# SCH_61.net
KiCad netlist of a schematic drawn in EasyEDA
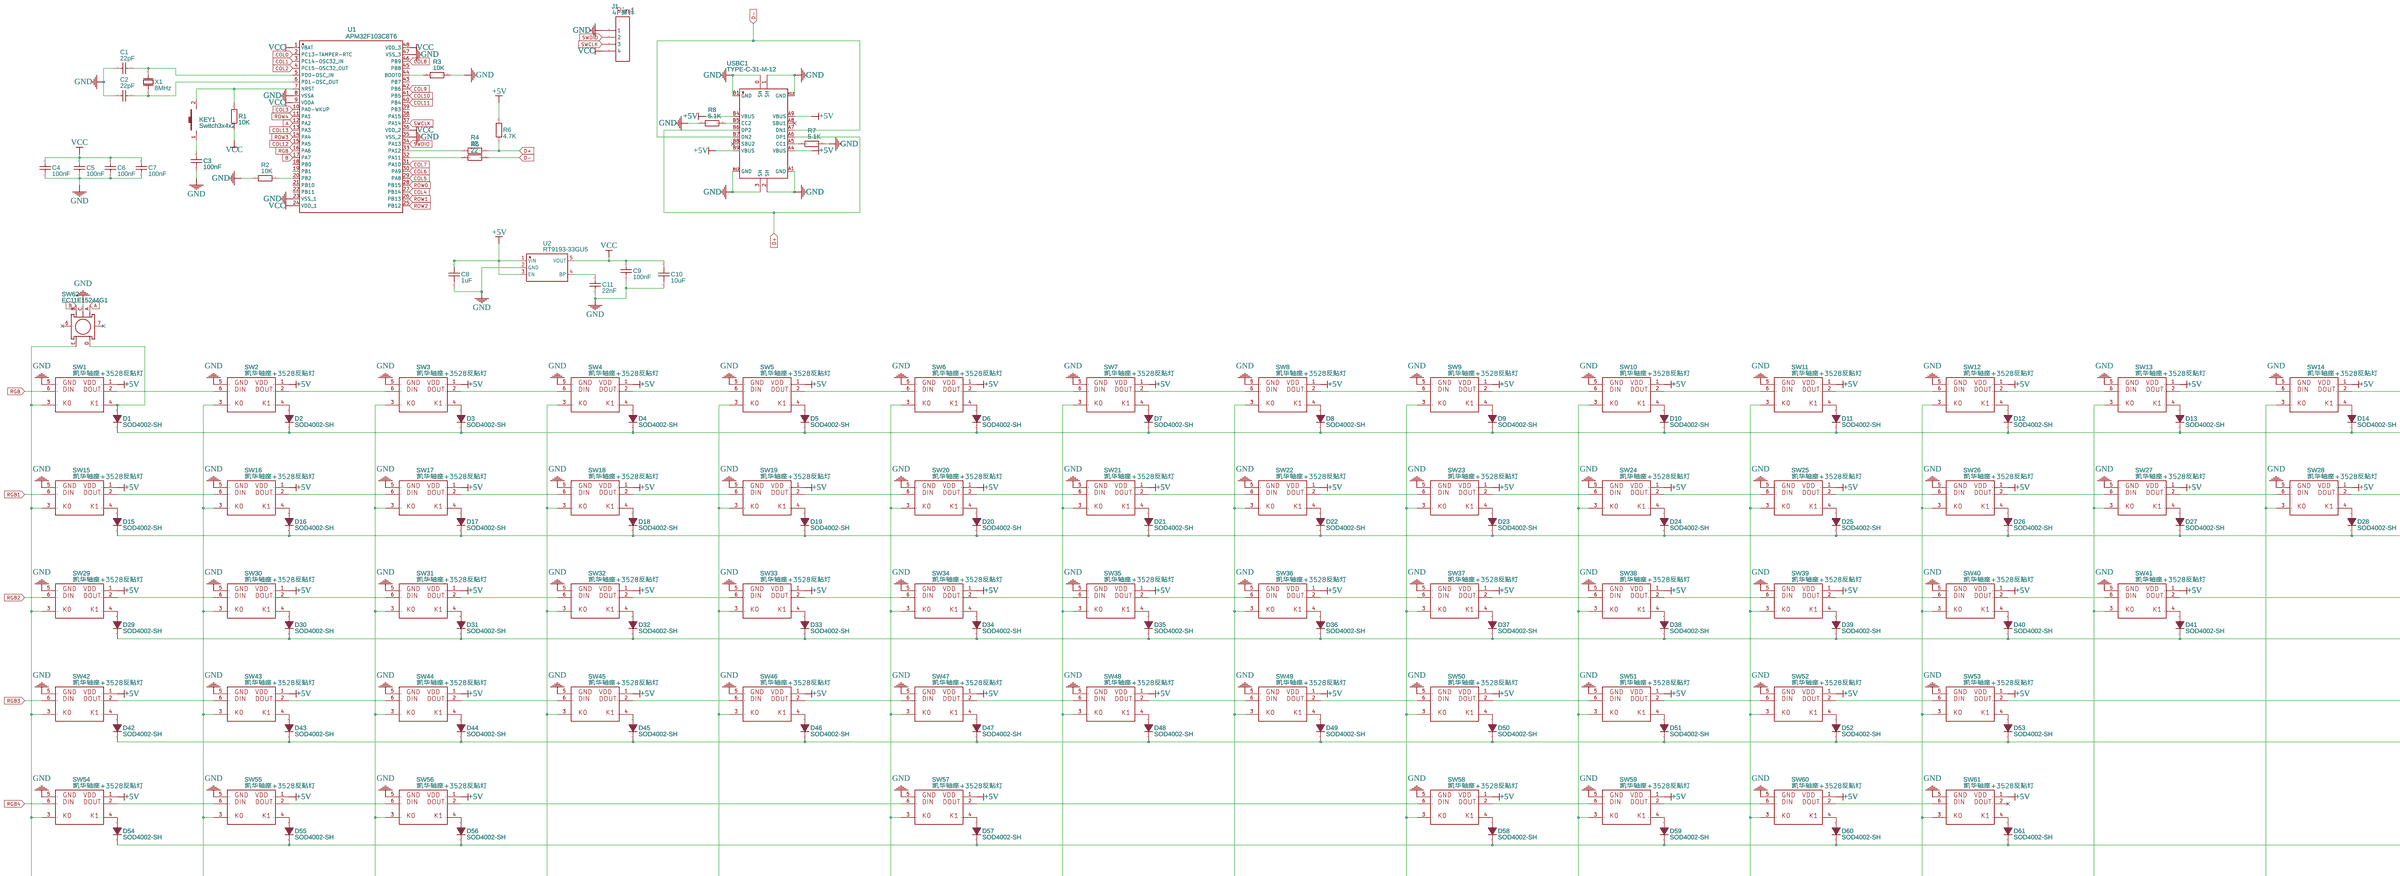
[diagram p0: schematic sheet]

(export (version "E")
  (design (tool "Eeschema 10.0.6"))
  (components
    (comp (ref "C1")
      (value "22pF")
      (fields
        (field (name "BOM_Manufacturer Part") "0805CG220J500NT")
        (field (name "BOM_Supplier Part") "C38143")
      )
      (libsource (lib "") (part "0805CG220J500NT"))
    )
    (comp (ref "C2")
      (value "22pF")
      (fields
        (field (name "BOM_Manufacturer Part") "0805CG220J500NT")
        (field (name "BOM_Supplier Part") "C38143")
      )
      (libsource (lib "") (part "0805CG220J500NT"))
    )
    (comp (ref "C3")
      (value "100nF")
      (fields
        (field (name "BOM_Manufacturer Part") "CL21B104KBCNNNC")
        (field (name "BOM_Supplier Part") "C1711")
      )
      (libsource (lib "") (part "CL21B104KBCNNNC"))
    )
    (comp (ref "C4")
      (value "100nF")
      (fields
        (field (name "BOM_Manufacturer Part") "CL21B104KBCNNNC")
        (field (name "BOM_Supplier Part") "C1711")
      )
      (libsource (lib "") (part "CL21B104KBCNNNC"))
    )
    (comp (ref "C5")
      (value "100nF")
      (fields
        (field (name "BOM_Manufacturer Part") "CL21B104KBCNNNC")
        (field (name "BOM_Supplier Part") "C1711")
      )
      (libsource (lib "") (part "CL21B104KBCNNNC"))
    )
    (comp (ref "C6")
      (value "100nF")
      (fields
        (field (name "BOM_Manufacturer Part") "CL21B104KBCNNNC")
        (field (name "BOM_Supplier Part") "C1711")
      )
      (libsource (lib "") (part "CL21B104KBCNNNC"))
    )
    (comp (ref "C7")
      (value "100nF")
      (fields
        (field (name "BOM_Manufacturer Part") "CL21B104KBCNNNC")
        (field (name "BOM_Supplier Part") "C1711")
      )
      (libsource (lib "") (part "CL21B104KBCNNNC"))
    )
    (comp (ref "C8")
      (value "1uF")
      (fields
        (field (name "BOM_Manufacturer Part") "CL21B105KBFVPNE")
        (field (name "BOM_Supplier Part") "C307362")
      )
      (libsource (lib "") (part "CL21B105KBFVPNE"))
    )
    (comp (ref "C9")
      (value "100nF")
      (fields
        (field (name "BOM_Manufacturer Part") "CL21B104KBCNNNC")
        (field (name "BOM_Supplier Part") "C1711")
      )
      (libsource (lib "") (part "CL21B104KBCNNNC"))
    )
    (comp (ref "C10")
      (value "10uF")
      (fields
        (field (name "BOM_Manufacturer Part") "CL21B106KPQNFNE")
        (field (name "BOM_Supplier Part") "C307538")
      )
      (libsource (lib "") (part "CL21B106KPQNFNE"))
    )
    (comp (ref "C11")
      (value "22nF")
      (fields
        (field (name "BOM_Manufacturer Part") "CL21B223KBANNNC")
        (field (name "BOM_Supplier Part") "C1729")
      )
      (libsource (lib "") (part "CL21B223KBANNNC"))
    )
    (comp (ref "D1")
      (value "SOD4002-SH")
      (fields (field (name "BOM_Supplier Part") "C154996"))
      (libsource (lib "") (part "SOD4002-SH"))
    )
    (comp (ref "D2")
      (value "SOD4002-SH")
      (fields (field (name "BOM_Supplier Part") "C154996"))
      (libsource (lib "") (part "SOD4002-SH"))
    )
    (comp (ref "D3")
      (value "SOD4002-SH")
      (fields (field (name "BOM_Supplier Part") "C154996"))
      (libsource (lib "") (part "SOD4002-SH"))
    )
    (comp (ref "D4")
      (value "SOD4002-SH")
      (fields (field (name "BOM_Supplier Part") "C154996"))
      (libsource (lib "") (part "SOD4002-SH"))
    )
    (comp (ref "D5")
      (value "SOD4002-SH")
      (fields (field (name "BOM_Supplier Part") "C154996"))
      (libsource (lib "") (part "SOD4002-SH"))
    )
    (comp (ref "D6")
      (value "SOD4002-SH")
      (fields (field (name "BOM_Supplier Part") "C154996"))
      (libsource (lib "") (part "SOD4002-SH"))
    )
    (comp (ref "D7")
      (value "SOD4002-SH")
      (fields (field (name "BOM_Supplier Part") "C154996"))
      (libsource (lib "") (part "SOD4002-SH"))
    )
    (comp (ref "D8")
      (value "SOD4002-SH")
      (fields (field (name "BOM_Supplier Part") "C154996"))
      (libsource (lib "") (part "SOD4002-SH"))
    )
    (comp (ref "D9")
      (value "SOD4002-SH")
      (fields (field (name "BOM_Supplier Part") "C154996"))
      (libsource (lib "") (part "SOD4002-SH"))
    )
    (comp (ref "D10")
      (value "SOD4002-SH")
      (fields (field (name "BOM_Supplier Part") "C154996"))
      (libsource (lib "") (part "SOD4002-SH"))
    )
    (comp (ref "D11")
      (value "SOD4002-SH")
      (fields (field (name "BOM_Supplier Part") "C154996"))
      (libsource (lib "") (part "SOD4002-SH"))
    )
    (comp (ref "D12")
      (value "SOD4002-SH")
      (fields (field (name "BOM_Supplier Part") "C154996"))
      (libsource (lib "") (part "SOD4002-SH"))
    )
    (comp (ref "D13")
      (value "SOD4002-SH")
      (fields (field (name "BOM_Supplier Part") "C154996"))
      (libsource (lib "") (part "SOD4002-SH"))
    )
    (comp (ref "D14")
      (value "SOD4002-SH")
      (fields (field (name "BOM_Supplier Part") "C154996"))
      (libsource (lib "") (part "SOD4002-SH"))
    )
    (comp (ref "D15")
      (value "SOD4002-SH")
      (fields (field (name "BOM_Supplier Part") "C154996"))
      (libsource (lib "") (part "SOD4002-SH"))
    )
    (comp (ref "D16")
      (value "SOD4002-SH")
      (fields (field (name "BOM_Supplier Part") "C154996"))
      (libsource (lib "") (part "SOD4002-SH"))
    )
    (comp (ref "D17")
      (value "SOD4002-SH")
      (fields (field (name "BOM_Supplier Part") "C154996"))
      (libsource (lib "") (part "SOD4002-SH"))
    )
    (comp (ref "D18")
      (value "SOD4002-SH")
      (fields (field (name "BOM_Supplier Part") "C154996"))
      (libsource (lib "") (part "SOD4002-SH"))
    )
    (comp (ref "D19")
      (value "SOD4002-SH")
      (fields (field (name "BOM_Supplier Part") "C154996"))
      (libsource (lib "") (part "SOD4002-SH"))
    )
    (comp (ref "D20")
      (value "SOD4002-SH")
      (fields (field (name "BOM_Supplier Part") "C154996"))
      (libsource (lib "") (part "SOD4002-SH"))
    )
    (comp (ref "D21")
      (value "SOD4002-SH")
      (fields (field (name "BOM_Supplier Part") "C154996"))
      (libsource (lib "") (part "SOD4002-SH"))
    )
    (comp (ref "D22")
      (value "SOD4002-SH")
      (fields (field (name "BOM_Supplier Part") "C154996"))
      (libsource (lib "") (part "SOD4002-SH"))
    )
    (comp (ref "D23")
      (value "SOD4002-SH")
      (fields (field (name "BOM_Supplier Part") "C154996"))
      (libsource (lib "") (part "SOD4002-SH"))
    )
    (comp (ref "D24")
      (value "SOD4002-SH")
      (fields (field (name "BOM_Supplier Part") "C154996"))
      (libsource (lib "") (part "SOD4002-SH"))
    )
    (comp (ref "D25")
      (value "SOD4002-SH")
      (fields (field (name "BOM_Supplier Part") "C154996"))
      (libsource (lib "") (part "SOD4002-SH"))
    )
    (comp (ref "D26")
      (value "SOD4002-SH")
      (fields (field (name "BOM_Supplier Part") "C154996"))
      (libsource (lib "") (part "SOD4002-SH"))
    )
    (comp (ref "D27")
      (value "SOD4002-SH")
      (fields (field (name "BOM_Supplier Part") "C154996"))
      (libsource (lib "") (part "SOD4002-SH"))
    )
    (comp (ref "D28")
      (value "SOD4002-SH")
      (fields (field (name "BOM_Supplier Part") "C154996"))
      (libsource (lib "") (part "SOD4002-SH"))
    )
    (comp (ref "D29")
      (value "SOD4002-SH")
      (fields (field (name "BOM_Supplier Part") "C154996"))
      (libsource (lib "") (part "SOD4002-SH"))
    )
    (comp (ref "D30")
      (value "SOD4002-SH")
      (fields (field (name "BOM_Supplier Part") "C154996"))
      (libsource (lib "") (part "SOD4002-SH"))
    )
    (comp (ref "D31")
      (value "SOD4002-SH")
      (fields (field (name "BOM_Supplier Part") "C154996"))
      (libsource (lib "") (part "SOD4002-SH"))
    )
    (comp (ref "D32")
      (value "SOD4002-SH")
      (fields (field (name "BOM_Supplier Part") "C154996"))
      (libsource (lib "") (part "SOD4002-SH"))
    )
    (comp (ref "D33")
      (value "SOD4002-SH")
      (fields (field (name "BOM_Supplier Part") "C154996"))
      (libsource (lib "") (part "SOD4002-SH"))
    )
    (comp (ref "D34")
      (value "SOD4002-SH")
      (fields (field (name "BOM_Supplier Part") "C154996"))
      (libsource (lib "") (part "SOD4002-SH"))
    )
    (comp (ref "D35")
      (value "SOD4002-SH")
      (fields (field (name "BOM_Supplier Part") "C154996"))
      (libsource (lib "") (part "SOD4002-SH"))
    )
    (comp (ref "D36")
      (value "SOD4002-SH")
      (fields (field (name "BOM_Supplier Part") "C154996"))
      (libsource (lib "") (part "SOD4002-SH"))
    )
    (comp (ref "D37")
      (value "SOD4002-SH")
      (fields (field (name "BOM_Supplier Part") "C154996"))
      (libsource (lib "") (part "SOD4002-SH"))
    )
    (comp (ref "D38")
      (value "SOD4002-SH")
      (fields (field (name "BOM_Supplier Part") "C154996"))
      (libsource (lib "") (part "SOD4002-SH"))
    )
    (comp (ref "D39")
      (value "SOD4002-SH")
      (fields (field (name "BOM_Supplier Part") "C154996"))
      (libsource (lib "") (part "SOD4002-SH"))
    )
    (comp (ref "D40")
      (value "SOD4002-SH")
      (fields (field (name "BOM_Supplier Part") "C154996"))
      (libsource (lib "") (part "SOD4002-SH"))
    )
    (comp (ref "D41")
      (value "SOD4002-SH")
      (fields (field (name "BOM_Supplier Part") "C154996"))
      (libsource (lib "") (part "SOD4002-SH"))
    )
    (comp (ref "D42")
      (value "SOD4002-SH")
      (fields (field (name "BOM_Supplier Part") "C154996"))
      (libsource (lib "") (part "SOD4002-SH"))
    )
    (comp (ref "D43")
      (value "SOD4002-SH")
      (fields (field (name "BOM_Supplier Part") "C154996"))
      (libsource (lib "") (part "SOD4002-SH"))
    )
    (comp (ref "D44")
      (value "SOD4002-SH")
      (fields (field (name "BOM_Supplier Part") "C154996"))
      (libsource (lib "") (part "SOD4002-SH"))
    )
    (comp (ref "D45")
      (value "SOD4002-SH")
      (fields (field (name "BOM_Supplier Part") "C154996"))
      (libsource (lib "") (part "SOD4002-SH"))
    )
    (comp (ref "D46")
      (value "SOD4002-SH")
      (fields (field (name "BOM_Supplier Part") "C154996"))
      (libsource (lib "") (part "SOD4002-SH"))
    )
    (comp (ref "D47")
      (value "SOD4002-SH")
      (fields (field (name "BOM_Supplier Part") "C154996"))
      (libsource (lib "") (part "SOD4002-SH"))
    )
    (comp (ref "D48")
      (value "SOD4002-SH")
      (fields (field (name "BOM_Supplier Part") "C154996"))
      (libsource (lib "") (part "SOD4002-SH"))
    )
    (comp (ref "D49")
      (value "SOD4002-SH")
      (fields (field (name "BOM_Supplier Part") "C154996"))
      (libsource (lib "") (part "SOD4002-SH"))
    )
    (comp (ref "D50")
      (value "SOD4002-SH")
      (fields (field (name "BOM_Supplier Part") "C154996"))
      (libsource (lib "") (part "SOD4002-SH"))
    )
    (comp (ref "D51")
      (value "SOD4002-SH")
      (fields (field (name "BOM_Supplier Part") "C154996"))
      (libsource (lib "") (part "SOD4002-SH"))
    )
    (comp (ref "D52")
      (value "SOD4002-SH")
      (fields (field (name "BOM_Supplier Part") "C154996"))
      (libsource (lib "") (part "SOD4002-SH"))
    )
    (comp (ref "D53")
      (value "SOD4002-SH")
      (fields (field (name "BOM_Supplier Part") "C154996"))
      (libsource (lib "") (part "SOD4002-SH"))
    )
    (comp (ref "D54")
      (value "SOD4002-SH")
      (fields (field (name "BOM_Supplier Part") "C154996"))
      (libsource (lib "") (part "SOD4002-SH"))
    )
    (comp (ref "D55")
      (value "SOD4002-SH")
      (fields (field (name "BOM_Supplier Part") "C154996"))
      (libsource (lib "") (part "SOD4002-SH"))
    )
    (comp (ref "D56")
      (value "SOD4002-SH")
      (fields (field (name "BOM_Supplier Part") "C154996"))
      (libsource (lib "") (part "SOD4002-SH"))
    )
    (comp (ref "D57")
      (value "SOD4002-SH")
      (fields (field (name "BOM_Supplier Part") "C154996"))
      (libsource (lib "") (part "SOD4002-SH"))
    )
    (comp (ref "D58")
      (value "SOD4002-SH")
      (fields (field (name "BOM_Supplier Part") "C154996"))
      (libsource (lib "") (part "SOD4002-SH"))
    )
    (comp (ref "D59")
      (value "SOD4002-SH")
      (fields (field (name "BOM_Supplier Part") "C154996"))
      (libsource (lib "") (part "SOD4002-SH"))
    )
    (comp (ref "D60")
      (value "SOD4002-SH")
      (fields (field (name "BOM_Supplier Part") "C154996"))
      (libsource (lib "") (part "SOD4002-SH"))
    )
    (comp (ref "D61")
      (value "SOD4002-SH")
      (fields (field (name "BOM_Supplier Part") "C154996"))
      (libsource (lib "") (part "SOD4002-SH"))
    )
    (comp (ref "J1") (value "4P排针") (libsource (lib "") (part "4P排针")))
    (comp (ref "KEY1")
      (value "Switch3x4x2")
      (fields (field (name "BOM_Supplier Part") "C26638"))
      (libsource (lib "") (part "Switch3x4x2"))
    )
    (comp (ref "R1")
      (value "10K")
      (fields
        (field (name "BOM_Manufacturer Part") "RC0805FR-0710KL")
        (field (name "BOM_Supplier Part") "C84376")
      )
      (libsource (lib "") (part "RC0805FR-0710KL"))
    )
    (comp (ref "R2")
      (value "10K")
      (fields
        (field (name "BOM_Manufacturer Part") "RC0805FR-0710KL")
        (field (name "BOM_Supplier Part") "C84376")
      )
      (libsource (lib "") (part "RC0805FR-0710KL_1"))
    )
    (comp (ref "R3")
      (value "10K")
      (fields
        (field (name "BOM_Manufacturer Part") "RC0805FR-0710KL")
        (field (name "BOM_Supplier Part") "C84376")
      )
      (libsource (lib "") (part "RC0805FR-0710KL_1"))
    )
    (comp (ref "R4")
      (value "22")
      (fields
        (field (name "BOM_Manufacturer Part") "RC0805FR-0722RL")
        (field (name "BOM_Supplier Part") "C107702")
      )
      (libsource (lib "") (part "RC0805FR-0722RL"))
    )
    (comp (ref "R5")
      (value "22")
      (fields
        (field (name "BOM_Manufacturer Part") "RC0805FR-0722RL")
        (field (name "BOM_Supplier Part") "C107702")
      )
      (libsource (lib "") (part "RC0805FR-0722RL"))
    )
    (comp (ref "R6")
      (value "4.7K")
      (fields
        (field (name "BOM_Manufacturer Part") "RC0805JR-074K7L")
        (field (name "BOM_Supplier Part") "C105427")
      )
      (libsource (lib "") (part "RC0805JR-074K7L"))
    )
    (comp (ref "R7")
      (value "5.1K")
      (fields
        (field (name "BOM_Manufacturer Part") "RC0805FR-075K1L")
        (field (name "BOM_Supplier Part") "C84375")
      )
      (libsource (lib "") (part "RC0805FR-075K1L"))
    )
    (comp (ref "R8")
      (value "5.1K")
      (fields
        (field (name "BOM_Manufacturer Part") "RC0805FR-075K1L")
        (field (name "BOM_Supplier Part") "C84375")
      )
      (libsource (lib "") (part "RC0805FR-075K1L"))
    )
    (comp (ref "SW1") (value "凯华轴座+3528反贴灯") (libsource (lib "") (part "凯华轴座+3528反贴灯")))
    (comp (ref "SW2") (value "凯华轴座+3528反贴灯") (libsource (lib "") (part "凯华轴座+3528反贴灯")))
    (comp (ref "SW3") (value "凯华轴座+3528反贴灯") (libsource (lib "") (part "凯华轴座+3528反贴灯")))
    (comp (ref "SW4") (value "凯华轴座+3528反贴灯") (libsource (lib "") (part "凯华轴座+3528反贴灯")))
    (comp (ref "SW5") (value "凯华轴座+3528反贴灯") (libsource (lib "") (part "凯华轴座+3528反贴灯")))
    (comp (ref "SW6") (value "凯华轴座+3528反贴灯") (libsource (lib "") (part "凯华轴座+3528反贴灯")))
    (comp (ref "SW7") (value "凯华轴座+3528反贴灯") (libsource (lib "") (part "凯华轴座+3528反贴灯")))
    (comp (ref "SW8") (value "凯华轴座+3528反贴灯") (libsource (lib "") (part "凯华轴座+3528反贴灯")))
    (comp (ref "SW9") (value "凯华轴座+3528反贴灯") (libsource (lib "") (part "凯华轴座+3528反贴灯")))
    (comp (ref "SW10") (value "凯华轴座+3528反贴灯") (libsource (lib "") (part "凯华轴座+3528反贴灯")))
    (comp (ref "SW11") (value "凯华轴座+3528反贴灯") (libsource (lib "") (part "凯华轴座+3528反贴灯")))
    (comp (ref "SW12") (value "凯华轴座+3528反贴灯") (libsource (lib "") (part "凯华轴座+3528反贴灯")))
    (comp (ref "SW13") (value "凯华轴座+3528反贴灯") (libsource (lib "") (part "凯华轴座+3528反贴灯")))
    (comp (ref "SW14") (value "凯华轴座+3528反贴灯") (libsource (lib "") (part "凯华轴座+3528反贴灯")))
    (comp (ref "SW15") (value "凯华轴座+3528反贴灯") (libsource (lib "") (part "凯华轴座+3528反贴灯")))
    (comp (ref "SW16") (value "凯华轴座+3528反贴灯") (libsource (lib "") (part "凯华轴座+3528反贴灯")))
    (comp (ref "SW17") (value "凯华轴座+3528反贴灯") (libsource (lib "") (part "凯华轴座+3528反贴灯")))
    (comp (ref "SW18") (value "凯华轴座+3528反贴灯") (libsource (lib "") (part "凯华轴座+3528反贴灯")))
    (comp (ref "SW19") (value "凯华轴座+3528反贴灯") (libsource (lib "") (part "凯华轴座+3528反贴灯")))
    (comp (ref "SW20") (value "凯华轴座+3528反贴灯") (libsource (lib "") (part "凯华轴座+3528反贴灯")))
    (comp (ref "SW21") (value "凯华轴座+3528反贴灯") (libsource (lib "") (part "凯华轴座+3528反贴灯")))
    (comp (ref "SW22") (value "凯华轴座+3528反贴灯") (libsource (lib "") (part "凯华轴座+3528反贴灯")))
    (comp (ref "SW23") (value "凯华轴座+3528反贴灯") (libsource (lib "") (part "凯华轴座+3528反贴灯")))
    (comp (ref "SW24") (value "凯华轴座+3528反贴灯") (libsource (lib "") (part "凯华轴座+3528反贴灯")))
    (comp (ref "SW25") (value "凯华轴座+3528反贴灯") (libsource (lib "") (part "凯华轴座+3528反贴灯")))
    (comp (ref "SW26") (value "凯华轴座+3528反贴灯") (libsource (lib "") (part "凯华轴座+3528反贴灯")))
    (comp (ref "SW27") (value "凯华轴座+3528反贴灯") (libsource (lib "") (part "凯华轴座+3528反贴灯")))
    (comp (ref "SW28") (value "凯华轴座+3528反贴灯") (libsource (lib "") (part "凯华轴座+3528反贴灯")))
    (comp (ref "SW29") (value "凯华轴座+3528反贴灯") (libsource (lib "") (part "凯华轴座+3528反贴灯")))
    (comp (ref "SW30") (value "凯华轴座+3528反贴灯") (libsource (lib "") (part "凯华轴座+3528反贴灯")))
    (comp (ref "SW31") (value "凯华轴座+3528反贴灯") (libsource (lib "") (part "凯华轴座+3528反贴灯")))
    (comp (ref "SW32") (value "凯华轴座+3528反贴灯") (libsource (lib "") (part "凯华轴座+3528反贴灯")))
    (comp (ref "SW33") (value "凯华轴座+3528反贴灯") (libsource (lib "") (part "凯华轴座+3528反贴灯")))
    (comp (ref "SW34") (value "凯华轴座+3528反贴灯") (libsource (lib "") (part "凯华轴座+3528反贴灯")))
    (comp (ref "SW35") (value "凯华轴座+3528反贴灯") (libsource (lib "") (part "凯华轴座+3528反贴灯")))
    (comp (ref "SW36") (value "凯华轴座+3528反贴灯") (libsource (lib "") (part "凯华轴座+3528反贴灯")))
    (comp (ref "SW37") (value "凯华轴座+3528反贴灯") (libsource (lib "") (part "凯华轴座+3528反贴灯")))
    (comp (ref "SW38") (value "凯华轴座+3528反贴灯") (libsource (lib "") (part "凯华轴座+3528反贴灯")))
    (comp (ref "SW39") (value "凯华轴座+3528反贴灯") (libsource (lib "") (part "凯华轴座+3528反贴灯")))
    (comp (ref "SW40") (value "凯华轴座+3528反贴灯") (libsource (lib "") (part "凯华轴座+3528反贴灯")))
    (comp (ref "SW41") (value "凯华轴座+3528反贴灯") (libsource (lib "") (part "凯华轴座+3528反贴灯")))
    (comp (ref "SW42") (value "凯华轴座+3528反贴灯") (libsource (lib "") (part "凯华轴座+3528反贴灯")))
    (comp (ref "SW43") (value "凯华轴座+3528反贴灯") (libsource (lib "") (part "凯华轴座+3528反贴灯")))
    (comp (ref "SW44") (value "凯华轴座+3528反贴灯") (libsource (lib "") (part "凯华轴座+3528反贴灯")))
    (comp (ref "SW45") (value "凯华轴座+3528反贴灯") (libsource (lib "") (part "凯华轴座+3528反贴灯")))
    (comp (ref "SW46") (value "凯华轴座+3528反贴灯") (libsource (lib "") (part "凯华轴座+3528反贴灯")))
    (comp (ref "SW47") (value "凯华轴座+3528反贴灯") (libsource (lib "") (part "凯华轴座+3528反贴灯")))
    (comp (ref "SW48") (value "凯华轴座+3528反贴灯") (libsource (lib "") (part "凯华轴座+3528反贴灯")))
    (comp (ref "SW49") (value "凯华轴座+3528反贴灯") (libsource (lib "") (part "凯华轴座+3528反贴灯")))
    (comp (ref "SW50") (value "凯华轴座+3528反贴灯") (libsource (lib "") (part "凯华轴座+3528反贴灯")))
    (comp (ref "SW51") (value "凯华轴座+3528反贴灯") (libsource (lib "") (part "凯华轴座+3528反贴灯")))
    (comp (ref "SW52") (value "凯华轴座+3528反贴灯") (libsource (lib "") (part "凯华轴座+3528反贴灯")))
    (comp (ref "SW53") (value "凯华轴座+3528反贴灯") (libsource (lib "") (part "凯华轴座+3528反贴灯")))
    (comp (ref "SW54") (value "凯华轴座+3528反贴灯") (libsource (lib "") (part "凯华轴座+3528反贴灯")))
    (comp (ref "SW55") (value "凯华轴座+3528反贴灯") (libsource (lib "") (part "凯华轴座+3528反贴灯")))
    (comp (ref "SW56") (value "凯华轴座+3528反贴灯") (libsource (lib "") (part "凯华轴座+3528反贴灯")))
    (comp (ref "SW57") (value "凯华轴座+3528反贴灯") (libsource (lib "") (part "凯华轴座+3528反贴灯")))
    (comp (ref "SW58") (value "凯华轴座+3528反贴灯") (libsource (lib "") (part "凯华轴座+3528反贴灯")))
    (comp (ref "SW59") (value "凯华轴座+3528反贴灯") (libsource (lib "") (part "凯华轴座+3528反贴灯")))
    (comp (ref "SW60") (value "凯华轴座+3528反贴灯") (libsource (lib "") (part "凯华轴座+3528反贴灯")))
    (comp (ref "SW61") (value "凯华轴座+3528反贴灯") (libsource (lib "") (part "凯华轴座+3528反贴灯")))
    (comp (ref "SW62")
      (value "EC11E15244G1")
      (fields (field (name "BOM_Supplier Part") "C370970"))
      (libsource (lib "") (part "EC11E15244G1"))
    )
    (comp (ref "U1")
      (value "APM32F103C8T6")
      (fields (field (name "BOM_Supplier Part") "C393540"))
      (libsource (lib "") (part "APM32F103C8T6"))
    )
    (comp (ref "U2")
      (value "RT9193-33GU5")
      (fields (field (name "BOM_Supplier Part") "C425797"))
      (libsource (lib "") (part "RT9193-33GU5"))
    )
    (comp (ref "USBC1")
      (value "TYPE-C-31-M-12")
      (fields (field (name "BOM_Supplier Part") "C165948"))
      (libsource (lib "") (part "TYPE-C-31-M-12"))
    )
    (comp (ref "X1")
      (value "8MHz")
      (fields
        (field (name "BOM_Manufacturer Part") "X50328MSB2GI")
        (field (name "BOM_Supplier Part") "C115962")
      )
      (libsource (lib "") (part "X50328MSB2GI"))
    )
  )
  (nets
    (net (code "1") (name "+5V") (class "Default")
      (node (ref "C8") (pin "2") (pinfunction "2_2") (pintype "unspecified"))
      (node (ref "R6") (pin "2") (pinfunction "2_2") (pintype "input"))
      (node (ref "SW1") (pin "1") (pinfunction "1_1") (pintype "unspecified"))
      (node (ref "SW10") (pin "1") (pinfunction "1_1") (pintype "unspecified"))
      (node (ref "SW11") (pin "1") (pinfunction "1_1") (pintype "unspecified"))
      (node (ref "SW12") (pin "1") (pinfunction "1_1") (pintype "unspecified"))
      (node (ref "SW13") (pin "1") (pinfunction "1_1") (pintype "unspecified"))
      (node (ref "SW14") (pin "1") (pinfunction "1_1") (pintype "unspecified"))
      (node (ref "SW15") (pin "1") (pinfunction "1_1") (pintype "unspecified"))
      (node (ref "SW16") (pin "1") (pinfunction "1_1") (pintype "unspecified"))
      (node (ref "SW17") (pin "1") (pinfunction "1_1") (pintype "unspecified"))
      (node (ref "SW18") (pin "1") (pinfunction "1_1") (pintype "unspecified"))
      (node (ref "SW19") (pin "1") (pinfunction "1_1") (pintype "unspecified"))
      (node (ref "SW2") (pin "1") (pinfunction "1_1") (pintype "unspecified"))
      (node (ref "SW20") (pin "1") (pinfunction "1_1") (pintype "unspecified"))
      (node (ref "SW21") (pin "1") (pinfunction "1_1") (pintype "unspecified"))
      (node (ref "SW22") (pin "1") (pinfunction "1_1") (pintype "unspecified"))
      (node (ref "SW23") (pin "1") (pinfunction "1_1") (pintype "unspecified"))
      (node (ref "SW24") (pin "1") (pinfunction "1_1") (pintype "unspecified"))
      (node (ref "SW25") (pin "1") (pinfunction "1_1") (pintype "unspecified"))
      (node (ref "SW26") (pin "1") (pinfunction "1_1") (pintype "unspecified"))
      (node (ref "SW27") (pin "1") (pinfunction "1_1") (pintype "unspecified"))
      (node (ref "SW28") (pin "1") (pinfunction "1_1") (pintype "unspecified"))
      (node (ref "SW29") (pin "1") (pinfunction "1_1") (pintype "unspecified"))
      (node (ref "SW3") (pin "1") (pinfunction "1_1") (pintype "unspecified"))
      (node (ref "SW30") (pin "1") (pinfunction "1_1") (pintype "unspecified"))
      (node (ref "SW31") (pin "1") (pinfunction "1_1") (pintype "unspecified"))
      (node (ref "SW32") (pin "1") (pinfunction "1_1") (pintype "unspecified"))
      (node (ref "SW33") (pin "1") (pinfunction "1_1") (pintype "unspecified"))
      (node (ref "SW34") (pin "1") (pinfunction "1_1") (pintype "unspecified"))
      (node (ref "SW35") (pin "1") (pinfunction "1_1") (pintype "unspecified"))
      (node (ref "SW36") (pin "1") (pinfunction "1_1") (pintype "unspecified"))
      (node (ref "SW37") (pin "1") (pinfunction "1_1") (pintype "unspecified"))
      (node (ref "SW38") (pin "1") (pinfunction "1_1") (pintype "unspecified"))
      (node (ref "SW39") (pin "1") (pinfunction "1_1") (pintype "unspecified"))
      (node (ref "SW4") (pin "1") (pinfunction "1_1") (pintype "unspecified"))
      (node (ref "SW40") (pin "1") (pinfunction "1_1") (pintype "unspecified"))
      (node (ref "SW41") (pin "1") (pinfunction "1_1") (pintype "unspecified"))
      (node (ref "SW42") (pin "1") (pinfunction "1_1") (pintype "unspecified"))
      (node (ref "SW43") (pin "1") (pinfunction "1_1") (pintype "unspecified"))
      (node (ref "SW44") (pin "1") (pinfunction "1_1") (pintype "unspecified"))
      (node (ref "SW45") (pin "1") (pinfunction "1_1") (pintype "unspecified"))
      (node (ref "SW46") (pin "1") (pinfunction "1_1") (pintype "unspecified"))
      (node (ref "SW47") (pin "1") (pinfunction "1_1") (pintype "unspecified"))
      (node (ref "SW48") (pin "1") (pinfunction "1_1") (pintype "unspecified"))
      (node (ref "SW49") (pin "1") (pinfunction "1_1") (pintype "unspecified"))
      (node (ref "SW5") (pin "1") (pinfunction "1_1") (pintype "unspecified"))
      (node (ref "SW50") (pin "1") (pinfunction "1_1") (pintype "unspecified"))
      (node (ref "SW51") (pin "1") (pinfunction "1_1") (pintype "unspecified"))
      (node (ref "SW52") (pin "1") (pinfunction "1_1") (pintype "unspecified"))
      (node (ref "SW53") (pin "1") (pinfunction "1_1") (pintype "unspecified"))
      (node (ref "SW54") (pin "1") (pinfunction "1_1") (pintype "unspecified"))
      (node (ref "SW55") (pin "1") (pinfunction "1_1") (pintype "unspecified"))
      (node (ref "SW56") (pin "1") (pinfunction "1_1") (pintype "unspecified"))
      (node (ref "SW57") (pin "1") (pinfunction "1_1") (pintype "unspecified"))
      (node (ref "SW58") (pin "1") (pinfunction "1_1") (pintype "unspecified"))
      (node (ref "SW59") (pin "1") (pinfunction "1_1") (pintype "unspecified"))
      (node (ref "SW6") (pin "1") (pinfunction "1_1") (pintype "unspecified"))
      (node (ref "SW60") (pin "1") (pinfunction "1_1") (pintype "unspecified"))
      (node (ref "SW61") (pin "1") (pinfunction "1_1") (pintype "unspecified"))
      (node (ref "SW7") (pin "1") (pinfunction "1_1") (pintype "unspecified"))
      (node (ref "SW8") (pin "1") (pinfunction "1_1") (pintype "unspecified"))
      (node (ref "SW9") (pin "1") (pinfunction "1_1") (pintype "unspecified"))
      (node (ref "U2") (pin "1") (pinfunction "VIN_1") (pintype "unspecified"))
      (node (ref "U2") (pin "3") (pinfunction "EN_3") (pintype "unspecified"))
      (node (ref "USBC1") (pin "A4") (pinfunction "VBUS_A4") (pintype "unspecified"))
      (node (ref "USBC1") (pin "A9") (pinfunction "VBUS_A9") (pintype "unspecified"))
      (node (ref "USBC1") (pin "B4") (pinfunction "VBUS_B4") (pintype "unspecified"))
      (node (ref "USBC1") (pin "B9") (pinfunction "VBUS_B9") (pintype "unspecified"))
    )
    (net (code "2") (name "A") (class "Default")
      (node (ref "SW62") (pin "A") (pinfunction "A_A") (pintype "unspecified"))
      (node (ref "U1") (pin "12") (pinfunction "PA2_12") (pintype "unspecified"))
    )
    (net (code "3") (name "B") (class "Default")
      (node (ref "SW62") (pin "B") (pinfunction "B_B") (pintype "unspecified"))
      (node (ref "U1") (pin "17") (pinfunction "PA7_17") (pintype "unspecified"))
    )
    (net (code "4") (name "COL0") (class "Default")
      (node (ref "SW1") (pin "3") (pinfunction "3_3") (pintype "unspecified"))
      (node (ref "SW15") (pin "3") (pinfunction "3_3") (pintype "unspecified"))
      (node (ref "SW29") (pin "3") (pinfunction "3_3") (pintype "unspecified"))
      (node (ref "SW42") (pin "3") (pinfunction "3_3") (pintype "unspecified"))
      (node (ref "SW54") (pin "3") (pinfunction "3_3") (pintype "unspecified"))
      (node (ref "SW62") (pin "E") (pinfunction "E_E") (pintype "unspecified"))
      (node (ref "U1") (pin "2") (pinfunction "PC13-TAMPER-RTC_2") (pintype "unspecified"))
    )
    (net (code "5") (name "COL1") (class "Default")
      (node (ref "SW16") (pin "3") (pinfunction "3_3") (pintype "unspecified"))
      (node (ref "SW2") (pin "3") (pinfunction "3_3") (pintype "unspecified"))
      (node (ref "SW30") (pin "3") (pinfunction "3_3") (pintype "unspecified"))
      (node (ref "SW43") (pin "3") (pinfunction "3_3") (pintype "unspecified"))
      (node (ref "SW55") (pin "3") (pinfunction "3_3") (pintype "unspecified"))
      (node (ref "U1") (pin "3") (pinfunction "PC14-OSC32_IN_3") (pintype "unspecified"))
    )
    (net (code "6") (name "COL2") (class "Default")
      (node (ref "SW17") (pin "3") (pinfunction "3_3") (pintype "unspecified"))
      (node (ref "SW3") (pin "3") (pinfunction "3_3") (pintype "unspecified"))
      (node (ref "SW31") (pin "3") (pinfunction "3_3") (pintype "unspecified"))
      (node (ref "SW44") (pin "3") (pinfunction "3_3") (pintype "unspecified"))
      (node (ref "SW56") (pin "3") (pinfunction "3_3") (pintype "unspecified"))
      (node (ref "U1") (pin "4") (pinfunction "PC15-OSC32_OUT_4") (pintype "unspecified"))
    )
    (net (code "7") (name "COL3") (class "Default")
      (node (ref "SW18") (pin "3") (pinfunction "3_3") (pintype "unspecified"))
      (node (ref "SW32") (pin "3") (pinfunction "3_3") (pintype "unspecified"))
      (node (ref "SW4") (pin "3") (pinfunction "3_3") (pintype "unspecified"))
      (node (ref "SW45") (pin "3") (pinfunction "3_3") (pintype "unspecified"))
      (node (ref "U1") (pin "10") (pinfunction "PA0-WKUP_10") (pintype "unspecified"))
    )
    (net (code "8") (name "COL4") (class "Default")
      (node (ref "SW19") (pin "3") (pinfunction "3_3") (pintype "unspecified"))
      (node (ref "SW33") (pin "3") (pinfunction "3_3") (pintype "unspecified"))
      (node (ref "SW46") (pin "3") (pinfunction "3_3") (pintype "unspecified"))
      (node (ref "SW5") (pin "3") (pinfunction "3_3") (pintype "unspecified"))
      (node (ref "U1") (pin "27") (pinfunction "PB14_27") (pintype "unspecified"))
    )
    (net (code "9") (name "COL5") (class "Default")
      (node (ref "SW20") (pin "3") (pinfunction "3_3") (pintype "unspecified"))
      (node (ref "SW34") (pin "3") (pinfunction "3_3") (pintype "unspecified"))
      (node (ref "SW47") (pin "3") (pinfunction "3_3") (pintype "unspecified"))
      (node (ref "SW57") (pin "3") (pinfunction "3_3") (pintype "unspecified"))
      (node (ref "SW6") (pin "3") (pinfunction "3_3") (pintype "unspecified"))
      (node (ref "U1") (pin "29") (pinfunction "PA8_29") (pintype "unspecified"))
    )
    (net (code "10") (name "COL6") (class "Default")
      (node (ref "SW21") (pin "3") (pinfunction "3_3") (pintype "unspecified"))
      (node (ref "SW35") (pin "3") (pinfunction "3_3") (pintype "unspecified"))
      (node (ref "SW48") (pin "3") (pinfunction "3_3") (pintype "unspecified"))
      (node (ref "SW7") (pin "3") (pinfunction "3_3") (pintype "unspecified"))
      (node (ref "U1") (pin "30") (pinfunction "PA9_30") (pintype "unspecified"))
    )
    (net (code "11") (name "COL7") (class "Default")
      (node (ref "SW22") (pin "3") (pinfunction "3_3") (pintype "unspecified"))
      (node (ref "SW36") (pin "3") (pinfunction "3_3") (pintype "unspecified"))
      (node (ref "SW49") (pin "3") (pinfunction "3_3") (pintype "unspecified"))
      (node (ref "SW8") (pin "3") (pinfunction "3_3") (pintype "unspecified"))
      (node (ref "U1") (pin "31") (pinfunction "PA10_31") (pintype "unspecified"))
    )
    (net (code "12") (name "COL8") (class "Default")
      (node (ref "SW23") (pin "3") (pinfunction "3_3") (pintype "unspecified"))
      (node (ref "SW37") (pin "3") (pinfunction "3_3") (pintype "unspecified"))
      (node (ref "SW50") (pin "3") (pinfunction "3_3") (pintype "unspecified"))
      (node (ref "SW58") (pin "3") (pinfunction "3_3") (pintype "unspecified"))
      (node (ref "SW9") (pin "3") (pinfunction "3_3") (pintype "unspecified"))
      (node (ref "U1") (pin "46") (pinfunction "PB9_46") (pintype "unspecified"))
    )
    (net (code "13") (name "COL9") (class "Default")
      (node (ref "SW10") (pin "3") (pinfunction "3_3") (pintype "unspecified"))
      (node (ref "SW24") (pin "3") (pinfunction "3_3") (pintype "unspecified"))
      (node (ref "SW38") (pin "3") (pinfunction "3_3") (pintype "unspecified"))
      (node (ref "SW51") (pin "3") (pinfunction "3_3") (pintype "unspecified"))
      (node (ref "SW59") (pin "3") (pinfunction "3_3") (pintype "unspecified"))
      (node (ref "U1") (pin "42") (pinfunction "PB6_42") (pintype "unspecified"))
    )
    (net (code "14") (name "COL10") (class "Default")
      (node (ref "SW11") (pin "3") (pinfunction "3_3") (pintype "unspecified"))
      (node (ref "SW25") (pin "3") (pinfunction "3_3") (pintype "unspecified"))
      (node (ref "SW39") (pin "3") (pinfunction "3_3") (pintype "unspecified"))
      (node (ref "SW52") (pin "3") (pinfunction "3_3") (pintype "unspecified"))
      (node (ref "SW60") (pin "3") (pinfunction "3_3") (pintype "unspecified"))
      (node (ref "U1") (pin "41") (pinfunction "PB5_41") (pintype "unspecified"))
    )
    (net (code "15") (name "COL11") (class "Default")
      (node (ref "SW12") (pin "3") (pinfunction "3_3") (pintype "unspecified"))
      (node (ref "SW26") (pin "3") (pinfunction "3_3") (pintype "unspecified"))
      (node (ref "SW40") (pin "3") (pinfunction "3_3") (pintype "unspecified"))
      (node (ref "SW53") (pin "3") (pinfunction "3_3") (pintype "unspecified"))
      (node (ref "SW61") (pin "3") (pinfunction "3_3") (pintype "unspecified"))
      (node (ref "U1") (pin "40") (pinfunction "PB4_40") (pintype "unspecified"))
    )
    (net (code "16") (name "COL12") (class "Default")
      (node (ref "SW13") (pin "3") (pinfunction "3_3") (pintype "unspecified"))
      (node (ref "SW27") (pin "3") (pinfunction "3_3") (pintype "unspecified"))
      (node (ref "SW41") (pin "3") (pinfunction "3_3") (pintype "unspecified"))
      (node (ref "U1") (pin "15") (pinfunction "PA5_15") (pintype "unspecified"))
    )
    (net (code "17") (name "COL13") (class "Default")
      (node (ref "SW14") (pin "3") (pinfunction "3_3") (pintype "unspecified"))
      (node (ref "SW28") (pin "3") (pinfunction "3_3") (pintype "unspecified"))
      (node (ref "U1") (pin "13") (pinfunction "PA3_13") (pintype "unspecified"))
    )
    (net (code "18") (name "D+") (class "Default")
      (node (ref "R4") (pin "2") (pinfunction "2_2") (pintype "input"))
      (node (ref "R6") (pin "1") (pinfunction "1_1") (pintype "input"))
      (node (ref "USBC1") (pin "A6") (pinfunction "DP1_A6") (pintype "unspecified"))
      (node (ref "USBC1") (pin "B6") (pinfunction "DP2_B6") (pintype "unspecified"))
    )
    (net (code "19") (name "D-") (class "Default")
      (node (ref "R5") (pin "2") (pinfunction "2_2") (pintype "input"))
      (node (ref "USBC1") (pin "A7") (pinfunction "DN1_A7") (pintype "unspecified"))
      (node (ref "USBC1") (pin "B7") (pinfunction "DN2_B7") (pintype "unspecified"))
    )
    (net (code "20") (name "GND") (class "Default")
      (node (ref "C1") (pin "1") (pinfunction "1_1") (pintype "input"))
      (node (ref "C10") (pin "2") (pinfunction "2_2") (pintype "unspecified"))
      (node (ref "C11") (pin "1") (pinfunction "1_1") (pintype "input"))
      (node (ref "C2") (pin "1") (pinfunction "1_1") (pintype "input"))
      (node (ref "C3") (pin "1") (pinfunction "1_1") (pintype "input"))
      (node (ref "C4") (pin "1") (pinfunction "1_1") (pintype "input"))
      (node (ref "C5") (pin "1") (pinfunction "1_1") (pintype "input"))
      (node (ref "C6") (pin "1") (pinfunction "1_1") (pintype "input"))
      (node (ref "C7") (pin "1") (pinfunction "1_1") (pintype "input"))
      (node (ref "C8") (pin "1") (pinfunction "1_1") (pintype "unspecified"))
      (node (ref "C9") (pin "1") (pinfunction "1_1") (pintype "input"))
      (node (ref "J1") (pin "1") (pinfunction "1_1") (pintype "unspecified"))
      (node (ref "R2") (pin "2") (pinfunction "2_2") (pintype "input"))
      (node (ref "R3") (pin "1") (pinfunction "1_1") (pintype "input"))
      (node (ref "R7") (pin "2") (pinfunction "2_2") (pintype "input"))
      (node (ref "R8") (pin "1") (pinfunction "1_1") (pintype "input"))
      (node (ref "SW1") (pin "5") (pinfunction "5_5") (pintype "unspecified"))
      (node (ref "SW10") (pin "5") (pinfunction "5_5") (pintype "unspecified"))
      (node (ref "SW11") (pin "5") (pinfunction "5_5") (pintype "unspecified"))
      (node (ref "SW12") (pin "5") (pinfunction "5_5") (pintype "unspecified"))
      (node (ref "SW13") (pin "5") (pinfunction "5_5") (pintype "unspecified"))
      (node (ref "SW14") (pin "5") (pinfunction "5_5") (pintype "unspecified"))
      (node (ref "SW15") (pin "5") (pinfunction "5_5") (pintype "unspecified"))
      (node (ref "SW16") (pin "5") (pinfunction "5_5") (pintype "unspecified"))
      (node (ref "SW17") (pin "5") (pinfunction "5_5") (pintype "unspecified"))
      (node (ref "SW18") (pin "5") (pinfunction "5_5") (pintype "unspecified"))
      (node (ref "SW19") (pin "5") (pinfunction "5_5") (pintype "unspecified"))
      (node (ref "SW2") (pin "5") (pinfunction "5_5") (pintype "unspecified"))
      (node (ref "SW20") (pin "5") (pinfunction "5_5") (pintype "unspecified"))
      (node (ref "SW21") (pin "5") (pinfunction "5_5") (pintype "unspecified"))
      (node (ref "SW22") (pin "5") (pinfunction "5_5") (pintype "unspecified"))
      (node (ref "SW23") (pin "5") (pinfunction "5_5") (pintype "unspecified"))
      (node (ref "SW24") (pin "5") (pinfunction "5_5") (pintype "unspecified"))
      (node (ref "SW25") (pin "5") (pinfunction "5_5") (pintype "unspecified"))
      (node (ref "SW26") (pin "5") (pinfunction "5_5") (pintype "unspecified"))
      (node (ref "SW27") (pin "5") (pinfunction "5_5") (pintype "unspecified"))
      (node (ref "SW28") (pin "5") (pinfunction "5_5") (pintype "unspecified"))
      (node (ref "SW29") (pin "5") (pinfunction "5_5") (pintype "unspecified"))
      (node (ref "SW3") (pin "5") (pinfunction "5_5") (pintype "unspecified"))
      (node (ref "SW30") (pin "5") (pinfunction "5_5") (pintype "unspecified"))
      (node (ref "SW31") (pin "5") (pinfunction "5_5") (pintype "unspecified"))
      (node (ref "SW32") (pin "5") (pinfunction "5_5") (pintype "unspecified"))
      (node (ref "SW33") (pin "5") (pinfunction "5_5") (pintype "unspecified"))
      (node (ref "SW34") (pin "5") (pinfunction "5_5") (pintype "unspecified"))
      (node (ref "SW35") (pin "5") (pinfunction "5_5") (pintype "unspecified"))
      (node (ref "SW36") (pin "5") (pinfunction "5_5") (pintype "unspecified"))
      (node (ref "SW37") (pin "5") (pinfunction "5_5") (pintype "unspecified"))
      (node (ref "SW38") (pin "5") (pinfunction "5_5") (pintype "unspecified"))
      (node (ref "SW39") (pin "5") (pinfunction "5_5") (pintype "unspecified"))
      (node (ref "SW4") (pin "5") (pinfunction "5_5") (pintype "unspecified"))
      (node (ref "SW40") (pin "5") (pinfunction "5_5") (pintype "unspecified"))
      (node (ref "SW41") (pin "5") (pinfunction "5_5") (pintype "unspecified"))
      (node (ref "SW42") (pin "5") (pinfunction "5_5") (pintype "unspecified"))
      (node (ref "SW43") (pin "5") (pinfunction "5_5") (pintype "unspecified"))
      (node (ref "SW44") (pin "5") (pinfunction "5_5") (pintype "unspecified"))
      (node (ref "SW45") (pin "5") (pinfunction "5_5") (pintype "unspecified"))
      (node (ref "SW46") (pin "5") (pinfunction "5_5") (pintype "unspecified"))
      (node (ref "SW47") (pin "5") (pinfunction "5_5") (pintype "unspecified"))
      (node (ref "SW48") (pin "5") (pinfunction "5_5") (pintype "unspecified"))
      (node (ref "SW49") (pin "5") (pinfunction "5_5") (pintype "unspecified"))
      (node (ref "SW5") (pin "5") (pinfunction "5_5") (pintype "unspecified"))
      (node (ref "SW50") (pin "5") (pinfunction "5_5") (pintype "unspecified"))
      (node (ref "SW51") (pin "5") (pinfunction "5_5") (pintype "unspecified"))
      (node (ref "SW52") (pin "5") (pinfunction "5_5") (pintype "unspecified"))
      (node (ref "SW53") (pin "5") (pinfunction "5_5") (pintype "unspecified"))
      (node (ref "SW54") (pin "5") (pinfunction "5_5") (pintype "unspecified"))
      (node (ref "SW55") (pin "5") (pinfunction "5_5") (pintype "unspecified"))
      (node (ref "SW56") (pin "5") (pinfunction "5_5") (pintype "unspecified"))
      (node (ref "SW57") (pin "5") (pinfunction "5_5") (pintype "unspecified"))
      (node (ref "SW58") (pin "5") (pinfunction "5_5") (pintype "unspecified"))
      (node (ref "SW59") (pin "5") (pinfunction "5_5") (pintype "unspecified"))
      (node (ref "SW6") (pin "5") (pinfunction "5_5") (pintype "unspecified"))
      (node (ref "SW60") (pin "5") (pinfunction "5_5") (pintype "unspecified"))
      (node (ref "SW61") (pin "5") (pinfunction "5_5") (pintype "unspecified"))
      (node (ref "SW62") (pin "C") (pinfunction "C_C") (pintype "unspecified"))
      (node (ref "SW7") (pin "5") (pinfunction "5_5") (pintype "unspecified"))
      (node (ref "SW8") (pin "5") (pinfunction "5_5") (pintype "unspecified"))
      (node (ref "SW9") (pin "5") (pinfunction "5_5") (pintype "unspecified"))
      (node (ref "U1") (pin "23") (pinfunction "VSS_1_23") (pintype "unspecified"))
      (node (ref "U1") (pin "35") (pinfunction "VSS_2_35") (pintype "unspecified"))
      (node (ref "U1") (pin "47") (pinfunction "VSS_3_47") (pintype "unspecified"))
      (node (ref "U1") (pin "8") (pinfunction "VSSA_8") (pintype "unspecified"))
      (node (ref "U2") (pin "2") (pinfunction "GND_2") (pintype "unspecified"))
      (node (ref "USBC1") (pin "0") (pinfunction "SH_0") (pintype "unspecified"))
      (node (ref "USBC1") (pin "1") (pinfunction "SH_1") (pintype "unspecified"))
      (node (ref "USBC1") (pin "2") (pinfunction "SH_2") (pintype "unspecified"))
      (node (ref "USBC1") (pin "3") (pinfunction "SH_3") (pintype "unspecified"))
      (node (ref "USBC1") (pin "A1") (pinfunction "GND_A1") (pintype "unspecified"))
      (node (ref "USBC1") (pin "A12") (pinfunction "GND_A12") (pintype "unspecified"))
      (node (ref "USBC1") (pin "B1") (pinfunction "GND_B1") (pintype "unspecified"))
      (node (ref "USBC1") (pin "B12") (pinfunction "GND_B12") (pintype "unspecified"))
    )
    (net (code "21") (name "Net-(C3-Pad2)") (class "Default")
      (node (ref "C3") (pin "2") (pinfunction "2_2") (pintype "input"))
      (node (ref "KEY1") (pin "1") (pinfunction "1_1") (pintype "input"))
    )
    (net (code "22") (name "Net-(D1-A)") (class "Default")
      (node (ref "D1") (pin "2") (pinfunction "A_2") (pintype "unspecified"))
      (node (ref "SW1") (pin "4") (pinfunction "4_4") (pintype "unspecified"))
      (node (ref "SW62") (pin "D") (pinfunction "D_D") (pintype "unspecified"))
    )
    (net (code "23") (name "Net-(D2-A)") (class "Default")
      (node (ref "D2") (pin "2") (pinfunction "A_2") (pintype "unspecified"))
      (node (ref "SW2") (pin "4") (pinfunction "4_4") (pintype "unspecified"))
    )
    (net (code "24") (name "Net-(D3-A)") (class "Default")
      (node (ref "D3") (pin "2") (pinfunction "A_2") (pintype "unspecified"))
      (node (ref "SW3") (pin "4") (pinfunction "4_4") (pintype "unspecified"))
    )
    (net (code "25") (name "Net-(D4-A)") (class "Default")
      (node (ref "D4") (pin "2") (pinfunction "A_2") (pintype "unspecified"))
      (node (ref "SW4") (pin "4") (pinfunction "4_4") (pintype "unspecified"))
    )
    (net (code "26") (name "Net-(D5-A)") (class "Default")
      (node (ref "D5") (pin "2") (pinfunction "A_2") (pintype "unspecified"))
      (node (ref "SW5") (pin "4") (pinfunction "4_4") (pintype "unspecified"))
    )
    (net (code "27") (name "Net-(D6-A)") (class "Default")
      (node (ref "D6") (pin "2") (pinfunction "A_2") (pintype "unspecified"))
      (node (ref "SW6") (pin "4") (pinfunction "4_4") (pintype "unspecified"))
    )
    (net (code "28") (name "Net-(D7-A)") (class "Default")
      (node (ref "D7") (pin "2") (pinfunction "A_2") (pintype "unspecified"))
      (node (ref "SW7") (pin "4") (pinfunction "4_4") (pintype "unspecified"))
    )
    (net (code "29") (name "Net-(D8-A)") (class "Default")
      (node (ref "D8") (pin "2") (pinfunction "A_2") (pintype "unspecified"))
      (node (ref "SW8") (pin "4") (pinfunction "4_4") (pintype "unspecified"))
    )
    (net (code "30") (name "Net-(D9-A)") (class "Default")
      (node (ref "D9") (pin "2") (pinfunction "A_2") (pintype "unspecified"))
      (node (ref "SW9") (pin "4") (pinfunction "4_4") (pintype "unspecified"))
    )
    (net (code "31") (name "Net-(D10-A)") (class "Default")
      (node (ref "D10") (pin "2") (pinfunction "A_2") (pintype "unspecified"))
      (node (ref "SW10") (pin "4") (pinfunction "4_4") (pintype "unspecified"))
    )
    (net (code "32") (name "Net-(D11-A)") (class "Default")
      (node (ref "D11") (pin "2") (pinfunction "A_2") (pintype "unspecified"))
      (node (ref "SW11") (pin "4") (pinfunction "4_4") (pintype "unspecified"))
    )
    (net (code "33") (name "Net-(D12-A)") (class "Default")
      (node (ref "D12") (pin "2") (pinfunction "A_2") (pintype "unspecified"))
      (node (ref "SW12") (pin "4") (pinfunction "4_4") (pintype "unspecified"))
    )
    (net (code "34") (name "Net-(D13-A)") (class "Default")
      (node (ref "D13") (pin "2") (pinfunction "A_2") (pintype "unspecified"))
      (node (ref "SW13") (pin "4") (pinfunction "4_4") (pintype "unspecified"))
    )
    (net (code "35") (name "Net-(D14-A)") (class "Default")
      (node (ref "D14") (pin "2") (pinfunction "A_2") (pintype "unspecified"))
      (node (ref "SW14") (pin "4") (pinfunction "4_4") (pintype "unspecified"))
    )
    (net (code "36") (name "Net-(D15-A)") (class "Default")
      (node (ref "D15") (pin "2") (pinfunction "A_2") (pintype "unspecified"))
      (node (ref "SW15") (pin "4") (pinfunction "4_4") (pintype "unspecified"))
    )
    (net (code "37") (name "Net-(D16-A)") (class "Default")
      (node (ref "D16") (pin "2") (pinfunction "A_2") (pintype "unspecified"))
      (node (ref "SW16") (pin "4") (pinfunction "4_4") (pintype "unspecified"))
    )
    (net (code "38") (name "Net-(D17-A)") (class "Default")
      (node (ref "D17") (pin "2") (pinfunction "A_2") (pintype "unspecified"))
      (node (ref "SW17") (pin "4") (pinfunction "4_4") (pintype "unspecified"))
    )
    (net (code "39") (name "Net-(D18-A)") (class "Default")
      (node (ref "D18") (pin "2") (pinfunction "A_2") (pintype "unspecified"))
      (node (ref "SW18") (pin "4") (pinfunction "4_4") (pintype "unspecified"))
    )
    (net (code "40") (name "Net-(D19-A)") (class "Default")
      (node (ref "D19") (pin "2") (pinfunction "A_2") (pintype "unspecified"))
      (node (ref "SW19") (pin "4") (pinfunction "4_4") (pintype "unspecified"))
    )
    (net (code "41") (name "Net-(D20-A)") (class "Default")
      (node (ref "D20") (pin "2") (pinfunction "A_2") (pintype "unspecified"))
      (node (ref "SW20") (pin "4") (pinfunction "4_4") (pintype "unspecified"))
    )
    (net (code "42") (name "Net-(D21-A)") (class "Default")
      (node (ref "D21") (pin "2") (pinfunction "A_2") (pintype "unspecified"))
      (node (ref "SW21") (pin "4") (pinfunction "4_4") (pintype "unspecified"))
    )
    (net (code "43") (name "Net-(D22-A)") (class "Default")
      (node (ref "D22") (pin "2") (pinfunction "A_2") (pintype "unspecified"))
      (node (ref "SW22") (pin "4") (pinfunction "4_4") (pintype "unspecified"))
    )
    (net (code "44") (name "Net-(D23-A)") (class "Default")
      (node (ref "D23") (pin "2") (pinfunction "A_2") (pintype "unspecified"))
      (node (ref "SW23") (pin "4") (pinfunction "4_4") (pintype "unspecified"))
    )
    (net (code "45") (name "Net-(D24-A)") (class "Default")
      (node (ref "D24") (pin "2") (pinfunction "A_2") (pintype "unspecified"))
      (node (ref "SW24") (pin "4") (pinfunction "4_4") (pintype "unspecified"))
    )
    (net (code "46") (name "Net-(D25-A)") (class "Default")
      (node (ref "D25") (pin "2") (pinfunction "A_2") (pintype "unspecified"))
      (node (ref "SW25") (pin "4") (pinfunction "4_4") (pintype "unspecified"))
    )
    (net (code "47") (name "Net-(D26-A)") (class "Default")
      (node (ref "D26") (pin "2") (pinfunction "A_2") (pintype "unspecified"))
      (node (ref "SW26") (pin "4") (pinfunction "4_4") (pintype "unspecified"))
    )
    (net (code "48") (name "Net-(D27-A)") (class "Default")
      (node (ref "D27") (pin "2") (pinfunction "A_2") (pintype "unspecified"))
      (node (ref "SW27") (pin "4") (pinfunction "4_4") (pintype "unspecified"))
    )
    (net (code "49") (name "Net-(D28-A)") (class "Default")
      (node (ref "D28") (pin "2") (pinfunction "A_2") (pintype "unspecified"))
      (node (ref "SW28") (pin "4") (pinfunction "4_4") (pintype "unspecified"))
    )
    (net (code "50") (name "Net-(D29-A)") (class "Default")
      (node (ref "D29") (pin "2") (pinfunction "A_2") (pintype "unspecified"))
      (node (ref "SW29") (pin "4") (pinfunction "4_4") (pintype "unspecified"))
    )
    (net (code "51") (name "Net-(D30-A)") (class "Default")
      (node (ref "D30") (pin "2") (pinfunction "A_2") (pintype "unspecified"))
      (node (ref "SW30") (pin "4") (pinfunction "4_4") (pintype "unspecified"))
    )
    (net (code "52") (name "Net-(D31-A)") (class "Default")
      (node (ref "D31") (pin "2") (pinfunction "A_2") (pintype "unspecified"))
      (node (ref "SW31") (pin "4") (pinfunction "4_4") (pintype "unspecified"))
    )
    (net (code "53") (name "Net-(D32-A)") (class "Default")
      (node (ref "D32") (pin "2") (pinfunction "A_2") (pintype "unspecified"))
      (node (ref "SW32") (pin "4") (pinfunction "4_4") (pintype "unspecified"))
    )
    (net (code "54") (name "Net-(D33-A)") (class "Default")
      (node (ref "D33") (pin "2") (pinfunction "A_2") (pintype "unspecified"))
      (node (ref "SW33") (pin "4") (pinfunction "4_4") (pintype "unspecified"))
    )
    (net (code "55") (name "Net-(D34-A)") (class "Default")
      (node (ref "D34") (pin "2") (pinfunction "A_2") (pintype "unspecified"))
      (node (ref "SW34") (pin "4") (pinfunction "4_4") (pintype "unspecified"))
    )
    (net (code "56") (name "Net-(D35-A)") (class "Default")
      (node (ref "D35") (pin "2") (pinfunction "A_2") (pintype "unspecified"))
      (node (ref "SW35") (pin "4") (pinfunction "4_4") (pintype "unspecified"))
    )
    (net (code "57") (name "Net-(D36-A)") (class "Default")
      (node (ref "D36") (pin "2") (pinfunction "A_2") (pintype "unspecified"))
      (node (ref "SW36") (pin "4") (pinfunction "4_4") (pintype "unspecified"))
    )
    (net (code "58") (name "Net-(D37-A)") (class "Default")
      (node (ref "D37") (pin "2") (pinfunction "A_2") (pintype "unspecified"))
      (node (ref "SW37") (pin "4") (pinfunction "4_4") (pintype "unspecified"))
    )
    (net (code "59") (name "Net-(D38-A)") (class "Default")
      (node (ref "D38") (pin "2") (pinfunction "A_2") (pintype "unspecified"))
      (node (ref "SW38") (pin "4") (pinfunction "4_4") (pintype "unspecified"))
    )
    (net (code "60") (name "Net-(D39-A)") (class "Default")
      (node (ref "D39") (pin "2") (pinfunction "A_2") (pintype "unspecified"))
      (node (ref "SW39") (pin "4") (pinfunction "4_4") (pintype "unspecified"))
    )
    (net (code "61") (name "Net-(D40-A)") (class "Default")
      (node (ref "D40") (pin "2") (pinfunction "A_2") (pintype "unspecified"))
      (node (ref "SW40") (pin "4") (pinfunction "4_4") (pintype "unspecified"))
    )
    (net (code "62") (name "Net-(D41-A)") (class "Default")
      (node (ref "D41") (pin "2") (pinfunction "A_2") (pintype "unspecified"))
      (node (ref "SW41") (pin "4") (pinfunction "4_4") (pintype "unspecified"))
    )
    (net (code "63") (name "Net-(D42-A)") (class "Default")
      (node (ref "D42") (pin "2") (pinfunction "A_2") (pintype "unspecified"))
      (node (ref "SW42") (pin "4") (pinfunction "4_4") (pintype "unspecified"))
    )
    (net (code "64") (name "Net-(D43-A)") (class "Default")
      (node (ref "D43") (pin "2") (pinfunction "A_2") (pintype "unspecified"))
      (node (ref "SW43") (pin "4") (pinfunction "4_4") (pintype "unspecified"))
    )
    (net (code "65") (name "Net-(D44-A)") (class "Default")
      (node (ref "D44") (pin "2") (pinfunction "A_2") (pintype "unspecified"))
      (node (ref "SW44") (pin "4") (pinfunction "4_4") (pintype "unspecified"))
    )
    (net (code "66") (name "Net-(D45-A)") (class "Default")
      (node (ref "D45") (pin "2") (pinfunction "A_2") (pintype "unspecified"))
      (node (ref "SW45") (pin "4") (pinfunction "4_4") (pintype "unspecified"))
    )
    (net (code "67") (name "Net-(D46-A)") (class "Default")
      (node (ref "D46") (pin "2") (pinfunction "A_2") (pintype "unspecified"))
      (node (ref "SW46") (pin "4") (pinfunction "4_4") (pintype "unspecified"))
    )
    (net (code "68") (name "Net-(D47-A)") (class "Default")
      (node (ref "D47") (pin "2") (pinfunction "A_2") (pintype "unspecified"))
      (node (ref "SW47") (pin "4") (pinfunction "4_4") (pintype "unspecified"))
    )
    (net (code "69") (name "Net-(D48-A)") (class "Default")
      (node (ref "D48") (pin "2") (pinfunction "A_2") (pintype "unspecified"))
      (node (ref "SW48") (pin "4") (pinfunction "4_4") (pintype "unspecified"))
    )
    (net (code "70") (name "Net-(D49-A)") (class "Default")
      (node (ref "D49") (pin "2") (pinfunction "A_2") (pintype "unspecified"))
      (node (ref "SW49") (pin "4") (pinfunction "4_4") (pintype "unspecified"))
    )
    (net (code "71") (name "Net-(D50-A)") (class "Default")
      (node (ref "D50") (pin "2") (pinfunction "A_2") (pintype "unspecified"))
      (node (ref "SW50") (pin "4") (pinfunction "4_4") (pintype "unspecified"))
    )
    (net (code "72") (name "Net-(D51-A)") (class "Default")
      (node (ref "D51") (pin "2") (pinfunction "A_2") (pintype "unspecified"))
      (node (ref "SW51") (pin "4") (pinfunction "4_4") (pintype "unspecified"))
    )
    (net (code "73") (name "Net-(D52-A)") (class "Default")
      (node (ref "D52") (pin "2") (pinfunction "A_2") (pintype "unspecified"))
      (node (ref "SW52") (pin "4") (pinfunction "4_4") (pintype "unspecified"))
    )
    (net (code "74") (name "Net-(D53-A)") (class "Default")
      (node (ref "D53") (pin "2") (pinfunction "A_2") (pintype "unspecified"))
      (node (ref "SW53") (pin "4") (pinfunction "4_4") (pintype "unspecified"))
    )
    (net (code "75") (name "Net-(D54-A)") (class "Default")
      (node (ref "D54") (pin "2") (pinfunction "A_2") (pintype "unspecified"))
      (node (ref "SW54") (pin "4") (pinfunction "4_4") (pintype "unspecified"))
    )
    (net (code "76") (name "Net-(D55-A)") (class "Default")
      (node (ref "D55") (pin "2") (pinfunction "A_2") (pintype "unspecified"))
      (node (ref "SW55") (pin "4") (pinfunction "4_4") (pintype "unspecified"))
    )
    (net (code "77") (name "Net-(D56-A)") (class "Default")
      (node (ref "D56") (pin "2") (pinfunction "A_2") (pintype "unspecified"))
      (node (ref "SW56") (pin "4") (pinfunction "4_4") (pintype "unspecified"))
    )
    (net (code "78") (name "Net-(D57-A)") (class "Default")
      (node (ref "D57") (pin "2") (pinfunction "A_2") (pintype "unspecified"))
      (node (ref "SW57") (pin "4") (pinfunction "4_4") (pintype "unspecified"))
    )
    (net (code "79") (name "Net-(D58-A)") (class "Default")
      (node (ref "D58") (pin "2") (pinfunction "A_2") (pintype "unspecified"))
      (node (ref "SW58") (pin "4") (pinfunction "4_4") (pintype "unspecified"))
    )
    (net (code "80") (name "Net-(D59-A)") (class "Default")
      (node (ref "D59") (pin "2") (pinfunction "A_2") (pintype "unspecified"))
      (node (ref "SW59") (pin "4") (pinfunction "4_4") (pintype "unspecified"))
    )
    (net (code "81") (name "Net-(D60-A)") (class "Default")
      (node (ref "D60") (pin "2") (pinfunction "A_2") (pintype "unspecified"))
      (node (ref "SW60") (pin "4") (pinfunction "4_4") (pintype "unspecified"))
    )
    (net (code "82") (name "Net-(D61-A)") (class "Default")
      (node (ref "D61") (pin "2") (pinfunction "A_2") (pintype "unspecified"))
      (node (ref "SW61") (pin "4") (pinfunction "4_4") (pintype "unspecified"))
    )
    (net (code "83") (name "Net-(SW1-Pad2)") (class "Default")
      (node (ref "SW1") (pin "2") (pinfunction "2_2") (pintype "unspecified"))
      (node (ref "SW2") (pin "6") (pinfunction "6_6") (pintype "unspecified"))
    )
    (net (code "84") (name "Net-(SW2-Pad2)") (class "Default")
      (node (ref "SW2") (pin "2") (pinfunction "2_2") (pintype "unspecified"))
      (node (ref "SW3") (pin "6") (pinfunction "6_6") (pintype "unspecified"))
    )
    (net (code "85") (name "Net-(SW3-Pad2)") (class "Default")
      (node (ref "SW3") (pin "2") (pinfunction "2_2") (pintype "unspecified"))
      (node (ref "SW4") (pin "6") (pinfunction "6_6") (pintype "unspecified"))
    )
    (net (code "86") (name "Net-(SW4-Pad2)") (class "Default")
      (node (ref "SW4") (pin "2") (pinfunction "2_2") (pintype "unspecified"))
      (node (ref "SW5") (pin "6") (pinfunction "6_6") (pintype "unspecified"))
    )
    (net (code "87") (name "Net-(SW5-Pad2)") (class "Default")
      (node (ref "SW5") (pin "2") (pinfunction "2_2") (pintype "unspecified"))
      (node (ref "SW6") (pin "6") (pinfunction "6_6") (pintype "unspecified"))
    )
    (net (code "88") (name "Net-(SW6-Pad2)") (class "Default")
      (node (ref "SW6") (pin "2") (pinfunction "2_2") (pintype "unspecified"))
      (node (ref "SW7") (pin "6") (pinfunction "6_6") (pintype "unspecified"))
    )
    (net (code "89") (name "Net-(SW7-Pad2)") (class "Default")
      (node (ref "SW7") (pin "2") (pinfunction "2_2") (pintype "unspecified"))
      (node (ref "SW8") (pin "6") (pinfunction "6_6") (pintype "unspecified"))
    )
    (net (code "90") (name "Net-(SW8-Pad2)") (class "Default")
      (node (ref "SW8") (pin "2") (pinfunction "2_2") (pintype "unspecified"))
      (node (ref "SW9") (pin "6") (pinfunction "6_6") (pintype "unspecified"))
    )
    (net (code "91") (name "Net-(SW10-Pad2)") (class "Default")
      (node (ref "SW10") (pin "2") (pinfunction "2_2") (pintype "unspecified"))
      (node (ref "SW11") (pin "6") (pinfunction "6_6") (pintype "unspecified"))
    )
    (net (code "92") (name "Net-(SW10-Pad6)") (class "Default")
      (node (ref "SW10") (pin "6") (pinfunction "6_6") (pintype "unspecified"))
      (node (ref "SW9") (pin "2") (pinfunction "2_2") (pintype "unspecified"))
    )
    (net (code "93") (name "Net-(SW11-Pad2)") (class "Default")
      (node (ref "SW11") (pin "2") (pinfunction "2_2") (pintype "unspecified"))
      (node (ref "SW12") (pin "6") (pinfunction "6_6") (pintype "unspecified"))
    )
    (net (code "94") (name "Net-(SW12-Pad2)") (class "Default")
      (node (ref "SW12") (pin "2") (pinfunction "2_2") (pintype "unspecified"))
      (node (ref "SW13") (pin "6") (pinfunction "6_6") (pintype "unspecified"))
    )
    (net (code "95") (name "Net-(SW13-Pad2)") (class "Default")
      (node (ref "SW13") (pin "2") (pinfunction "2_2") (pintype "unspecified"))
      (node (ref "SW14") (pin "6") (pinfunction "6_6") (pintype "unspecified"))
    )
    (net (code "96") (name "Net-(SW15-Pad2)") (class "Default")
      (node (ref "SW15") (pin "2") (pinfunction "2_2") (pintype "unspecified"))
      (node (ref "SW16") (pin "6") (pinfunction "6_6") (pintype "unspecified"))
    )
    (net (code "97") (name "Net-(SW16-Pad2)") (class "Default")
      (node (ref "SW16") (pin "2") (pinfunction "2_2") (pintype "unspecified"))
      (node (ref "SW17") (pin "6") (pinfunction "6_6") (pintype "unspecified"))
    )
    (net (code "98") (name "Net-(SW17-Pad2)") (class "Default")
      (node (ref "SW17") (pin "2") (pinfunction "2_2") (pintype "unspecified"))
      (node (ref "SW18") (pin "6") (pinfunction "6_6") (pintype "unspecified"))
    )
    (net (code "99") (name "Net-(SW18-Pad2)") (class "Default")
      (node (ref "SW18") (pin "2") (pinfunction "2_2") (pintype "unspecified"))
      (node (ref "SW19") (pin "6") (pinfunction "6_6") (pintype "unspecified"))
    )
    (net (code "100") (name "Net-(SW19-Pad2)") (class "Default")
      (node (ref "SW19") (pin "2") (pinfunction "2_2") (pintype "unspecified"))
      (node (ref "SW20") (pin "6") (pinfunction "6_6") (pintype "unspecified"))
    )
    (net (code "101") (name "Net-(SW20-Pad2)") (class "Default")
      (node (ref "SW20") (pin "2") (pinfunction "2_2") (pintype "unspecified"))
      (node (ref "SW21") (pin "6") (pinfunction "6_6") (pintype "unspecified"))
    )
    (net (code "102") (name "Net-(SW21-Pad2)") (class "Default")
      (node (ref "SW21") (pin "2") (pinfunction "2_2") (pintype "unspecified"))
      (node (ref "SW22") (pin "6") (pinfunction "6_6") (pintype "unspecified"))
    )
    (net (code "103") (name "Net-(SW22-Pad2)") (class "Default")
      (node (ref "SW22") (pin "2") (pinfunction "2_2") (pintype "unspecified"))
      (node (ref "SW23") (pin "6") (pinfunction "6_6") (pintype "unspecified"))
    )
    (net (code "104") (name "Net-(SW23-Pad2)") (class "Default")
      (node (ref "SW23") (pin "2") (pinfunction "2_2") (pintype "unspecified"))
      (node (ref "SW24") (pin "6") (pinfunction "6_6") (pintype "unspecified"))
    )
    (net (code "105") (name "Net-(SW24-Pad2)") (class "Default")
      (node (ref "SW24") (pin "2") (pinfunction "2_2") (pintype "unspecified"))
      (node (ref "SW25") (pin "6") (pinfunction "6_6") (pintype "unspecified"))
    )
    (net (code "106") (name "Net-(SW25-Pad2)") (class "Default")
      (node (ref "SW25") (pin "2") (pinfunction "2_2") (pintype "unspecified"))
      (node (ref "SW26") (pin "6") (pinfunction "6_6") (pintype "unspecified"))
    )
    (net (code "107") (name "Net-(SW26-Pad2)") (class "Default")
      (node (ref "SW26") (pin "2") (pinfunction "2_2") (pintype "unspecified"))
      (node (ref "SW27") (pin "6") (pinfunction "6_6") (pintype "unspecified"))
    )
    (net (code "108") (name "Net-(SW27-Pad2)") (class "Default")
      (node (ref "SW27") (pin "2") (pinfunction "2_2") (pintype "unspecified"))
      (node (ref "SW28") (pin "6") (pinfunction "6_6") (pintype "unspecified"))
    )
    (net (code "109") (name "Net-(SW29-Pad2)") (class "Default")
      (node (ref "SW29") (pin "2") (pinfunction "2_2") (pintype "unspecified"))
      (node (ref "SW30") (pin "6") (pinfunction "6_6") (pintype "unspecified"))
    )
    (net (code "110") (name "Net-(SW30-Pad2)") (class "Default")
      (node (ref "SW30") (pin "2") (pinfunction "2_2") (pintype "unspecified"))
      (node (ref "SW31") (pin "6") (pinfunction "6_6") (pintype "unspecified"))
    )
    (net (code "111") (name "Net-(SW31-Pad2)") (class "Default")
      (node (ref "SW31") (pin "2") (pinfunction "2_2") (pintype "unspecified"))
      (node (ref "SW32") (pin "6") (pinfunction "6_6") (pintype "unspecified"))
    )
    (net (code "112") (name "Net-(SW32-Pad2)") (class "Default")
      (node (ref "SW32") (pin "2") (pinfunction "2_2") (pintype "unspecified"))
      (node (ref "SW33") (pin "6") (pinfunction "6_6") (pintype "unspecified"))
    )
    (net (code "113") (name "Net-(SW33-Pad2)") (class "Default")
      (node (ref "SW33") (pin "2") (pinfunction "2_2") (pintype "unspecified"))
      (node (ref "SW34") (pin "6") (pinfunction "6_6") (pintype "unspecified"))
    )
    (net (code "114") (name "Net-(SW34-Pad2)") (class "Default")
      (node (ref "SW34") (pin "2") (pinfunction "2_2") (pintype "unspecified"))
      (node (ref "SW35") (pin "6") (pinfunction "6_6") (pintype "unspecified"))
    )
    (net (code "115") (name "Net-(SW35-Pad2)") (class "Default")
      (node (ref "SW35") (pin "2") (pinfunction "2_2") (pintype "unspecified"))
      (node (ref "SW36") (pin "6") (pinfunction "6_6") (pintype "unspecified"))
    )
    (net (code "116") (name "Net-(SW36-Pad2)") (class "Default")
      (node (ref "SW36") (pin "2") (pinfunction "2_2") (pintype "unspecified"))
      (node (ref "SW37") (pin "6") (pinfunction "6_6") (pintype "unspecified"))
    )
    (net (code "117") (name "Net-(SW37-Pad2)") (class "Default")
      (node (ref "SW37") (pin "2") (pinfunction "2_2") (pintype "unspecified"))
      (node (ref "SW38") (pin "6") (pinfunction "6_6") (pintype "unspecified"))
    )
    (net (code "118") (name "Net-(SW38-Pad2)") (class "Default")
      (node (ref "SW38") (pin "2") (pinfunction "2_2") (pintype "unspecified"))
      (node (ref "SW39") (pin "6") (pinfunction "6_6") (pintype "unspecified"))
    )
    (net (code "119") (name "Net-(SW39-Pad2)") (class "Default")
      (node (ref "SW39") (pin "2") (pinfunction "2_2") (pintype "unspecified"))
      (node (ref "SW40") (pin "6") (pinfunction "6_6") (pintype "unspecified"))
    )
    (net (code "120") (name "Net-(SW40-Pad2)") (class "Default")
      (node (ref "SW40") (pin "2") (pinfunction "2_2") (pintype "unspecified"))
      (node (ref "SW41") (pin "6") (pinfunction "6_6") (pintype "unspecified"))
    )
    (net (code "121") (name "Net-(SW42-Pad2)") (class "Default")
      (node (ref "SW42") (pin "2") (pinfunction "2_2") (pintype "unspecified"))
      (node (ref "SW43") (pin "6") (pinfunction "6_6") (pintype "unspecified"))
    )
    (net (code "122") (name "Net-(SW43-Pad2)") (class "Default")
      (node (ref "SW43") (pin "2") (pinfunction "2_2") (pintype "unspecified"))
      (node (ref "SW44") (pin "6") (pinfunction "6_6") (pintype "unspecified"))
    )
    (net (code "123") (name "Net-(SW44-Pad2)") (class "Default")
      (node (ref "SW44") (pin "2") (pinfunction "2_2") (pintype "unspecified"))
      (node (ref "SW45") (pin "6") (pinfunction "6_6") (pintype "unspecified"))
    )
    (net (code "124") (name "Net-(SW45-Pad2)") (class "Default")
      (node (ref "SW45") (pin "2") (pinfunction "2_2") (pintype "unspecified"))
      (node (ref "SW46") (pin "6") (pinfunction "6_6") (pintype "unspecified"))
    )
    (net (code "125") (name "Net-(SW46-Pad2)") (class "Default")
      (node (ref "SW46") (pin "2") (pinfunction "2_2") (pintype "unspecified"))
      (node (ref "SW47") (pin "6") (pinfunction "6_6") (pintype "unspecified"))
    )
    (net (code "126") (name "Net-(SW47-Pad2)") (class "Default")
      (node (ref "SW47") (pin "2") (pinfunction "2_2") (pintype "unspecified"))
      (node (ref "SW48") (pin "6") (pinfunction "6_6") (pintype "unspecified"))
    )
    (net (code "127") (name "Net-(SW48-Pad2)") (class "Default")
      (node (ref "SW48") (pin "2") (pinfunction "2_2") (pintype "unspecified"))
      (node (ref "SW49") (pin "6") (pinfunction "6_6") (pintype "unspecified"))
    )
    (net (code "128") (name "Net-(SW49-Pad2)") (class "Default")
      (node (ref "SW49") (pin "2") (pinfunction "2_2") (pintype "unspecified"))
      (node (ref "SW50") (pin "6") (pinfunction "6_6") (pintype "unspecified"))
    )
    (net (code "129") (name "Net-(SW50-Pad2)") (class "Default")
      (node (ref "SW50") (pin "2") (pinfunction "2_2") (pintype "unspecified"))
      (node (ref "SW51") (pin "6") (pinfunction "6_6") (pintype "unspecified"))
    )
    (net (code "130") (name "Net-(SW51-Pad2)") (class "Default")
      (node (ref "SW51") (pin "2") (pinfunction "2_2") (pintype "unspecified"))
      (node (ref "SW52") (pin "6") (pinfunction "6_6") (pintype "unspecified"))
    )
    (net (code "131") (name "Net-(SW52-Pad2)") (class "Default")
      (node (ref "SW52") (pin "2") (pinfunction "2_2") (pintype "unspecified"))
      (node (ref "SW53") (pin "6") (pinfunction "6_6") (pintype "unspecified"))
    )
    (net (code "132") (name "Net-(SW54-Pad2)") (class "Default")
      (node (ref "SW54") (pin "2") (pinfunction "2_2") (pintype "unspecified"))
      (node (ref "SW55") (pin "6") (pinfunction "6_6") (pintype "unspecified"))
    )
    (net (code "133") (name "Net-(SW55-Pad2)") (class "Default")
      (node (ref "SW55") (pin "2") (pinfunction "2_2") (pintype "unspecified"))
      (node (ref "SW56") (pin "6") (pinfunction "6_6") (pintype "unspecified"))
    )
    (net (code "134") (name "Net-(SW56-Pad2)") (class "Default")
      (node (ref "SW56") (pin "2") (pinfunction "2_2") (pintype "unspecified"))
      (node (ref "SW57") (pin "6") (pinfunction "6_6") (pintype "unspecified"))
    )
    (net (code "135") (name "Net-(SW57-Pad2)") (class "Default")
      (node (ref "SW57") (pin "2") (pinfunction "2_2") (pintype "unspecified"))
      (node (ref "SW58") (pin "6") (pinfunction "6_6") (pintype "unspecified"))
    )
    (net (code "136") (name "Net-(SW58-Pad2)") (class "Default")
      (node (ref "SW58") (pin "2") (pinfunction "2_2") (pintype "unspecified"))
      (node (ref "SW59") (pin "6") (pinfunction "6_6") (pintype "unspecified"))
    )
    (net (code "137") (name "Net-(SW59-Pad2)") (class "Default")
      (node (ref "SW59") (pin "2") (pinfunction "2_2") (pintype "unspecified"))
      (node (ref "SW60") (pin "6") (pinfunction "6_6") (pintype "unspecified"))
    )
    (net (code "138") (name "Net-(SW60-Pad2)") (class "Default")
      (node (ref "SW60") (pin "2") (pinfunction "2_2") (pintype "unspecified"))
      (node (ref "SW61") (pin "6") (pinfunction "6_6") (pintype "unspecified"))
    )
    (net (code "139") (name "Net-(U1-BOOT0)") (class "Default")
      (node (ref "R3") (pin "2") (pinfunction "2_2") (pintype "input"))
      (node (ref "U1") (pin "44") (pinfunction "BOOT0_44") (pintype "unspecified"))
    )
    (net (code "140") (name "Net-(U1-NRST)") (class "Default")
      (node (ref "KEY1") (pin "2") (pinfunction "2_2") (pintype "input"))
      (node (ref "R1") (pin "2") (pinfunction "2_2") (pintype "input"))
      (node (ref "U1") (pin "7") (pinfunction "NRST_7") (pintype "unspecified"))
    )
    (net (code "141") (name "Net-(U1-PA11)") (class "Default")
      (node (ref "R5") (pin "1") (pinfunction "1_1") (pintype "input"))
      (node (ref "U1") (pin "32") (pinfunction "PA11_32") (pintype "unspecified"))
    )
    (net (code "142") (name "Net-(U1-PA12)") (class "Default")
      (node (ref "R4") (pin "1") (pinfunction "1_1") (pintype "input"))
      (node (ref "U1") (pin "33") (pinfunction "PA12_33") (pintype "unspecified"))
    )
    (net (code "143") (name "Net-(U1-PB2)") (class "Default")
      (node (ref "R2") (pin "1") (pinfunction "1_1") (pintype "input"))
      (node (ref "U1") (pin "20") (pinfunction "PB2_20") (pintype "unspecified"))
    )
    (net (code "144") (name "Net-(U1-PD0-OSC_IN)") (class "Default")
      (node (ref "C1") (pin "2") (pinfunction "2_2") (pintype "input"))
      (node (ref "U1") (pin "5") (pinfunction "PD0-OSC_IN_5") (pintype "unspecified"))
      (node (ref "X1") (pin "2") (pinfunction "OSC2_2") (pintype "input"))
    )
    (net (code "145") (name "Net-(U1-PD1-OSC_OUT)") (class "Default")
      (node (ref "C2") (pin "2") (pinfunction "2_2") (pintype "input"))
      (node (ref "U1") (pin "6") (pinfunction "PD1-OSC_OUT_6") (pintype "unspecified"))
      (node (ref "X1") (pin "1") (pinfunction "OSC1_1") (pintype "input"))
    )
    (net (code "146") (name "Net-(U2-BP)") (class "Default")
      (node (ref "C11") (pin "2") (pinfunction "2_2") (pintype "input"))
      (node (ref "U2") (pin "4") (pinfunction "BP_4") (pintype "unspecified"))
    )
    (net (code "147") (name "Net-(USBC1-CC1)") (class "Default")
      (node (ref "R7") (pin "1") (pinfunction "1_1") (pintype "input"))
      (node (ref "USBC1") (pin "A5") (pinfunction "CC1_A5") (pintype "unspecified"))
    )
    (net (code "148") (name "Net-(USBC1-CC2)") (class "Default")
      (node (ref "R8") (pin "2") (pinfunction "2_2") (pintype "input"))
      (node (ref "USBC1") (pin "B5") (pinfunction "CC2_B5") (pintype "unspecified"))
    )
    (net (code "149") (name "RGB") (class "Default")
      (node (ref "SW1") (pin "6") (pinfunction "6_6") (pintype "unspecified"))
      (node (ref "U1") (pin "16") (pinfunction "PA6_16") (pintype "unspecified"))
    )
    (net (code "150") (name "RGB1") (class "Default")
      (node (ref "SW14") (pin "2") (pinfunction "2_2") (pintype "unspecified"))
      (node (ref "SW15") (pin "6") (pinfunction "6_6") (pintype "unspecified"))
    )
    (net (code "151") (name "RGB2") (class "Default")
      (node (ref "SW28") (pin "2") (pinfunction "2_2") (pintype "unspecified"))
      (node (ref "SW29") (pin "6") (pinfunction "6_6") (pintype "unspecified"))
    )
    (net (code "152") (name "RGB3") (class "Default")
      (node (ref "SW41") (pin "2") (pinfunction "2_2") (pintype "unspecified"))
      (node (ref "SW42") (pin "6") (pinfunction "6_6") (pintype "unspecified"))
    )
    (net (code "153") (name "RGB4") (class "Default")
      (node (ref "SW53") (pin "2") (pinfunction "2_2") (pintype "unspecified"))
      (node (ref "SW54") (pin "6") (pinfunction "6_6") (pintype "unspecified"))
    )
    (net (code "154") (name "ROW0") (class "Default")
      (node (ref "D1") (pin "1") (pinfunction "K_1") (pintype "unspecified"))
      (node (ref "D10") (pin "1") (pinfunction "K_1") (pintype "unspecified"))
      (node (ref "D11") (pin "1") (pinfunction "K_1") (pintype "unspecified"))
      (node (ref "D12") (pin "1") (pinfunction "K_1") (pintype "unspecified"))
      (node (ref "D13") (pin "1") (pinfunction "K_1") (pintype "unspecified"))
      (node (ref "D14") (pin "1") (pinfunction "K_1") (pintype "unspecified"))
      (node (ref "D2") (pin "1") (pinfunction "K_1") (pintype "unspecified"))
      (node (ref "D3") (pin "1") (pinfunction "K_1") (pintype "unspecified"))
      (node (ref "D4") (pin "1") (pinfunction "K_1") (pintype "unspecified"))
      (node (ref "D5") (pin "1") (pinfunction "K_1") (pintype "unspecified"))
      (node (ref "D6") (pin "1") (pinfunction "K_1") (pintype "unspecified"))
      (node (ref "D7") (pin "1") (pinfunction "K_1") (pintype "unspecified"))
      (node (ref "D8") (pin "1") (pinfunction "K_1") (pintype "unspecified"))
      (node (ref "D9") (pin "1") (pinfunction "K_1") (pintype "unspecified"))
      (node (ref "U1") (pin "28") (pinfunction "PB15_28") (pintype "unspecified"))
    )
    (net (code "155") (name "ROW1") (class "Default")
      (node (ref "D15") (pin "1") (pinfunction "K_1") (pintype "unspecified"))
      (node (ref "D16") (pin "1") (pinfunction "K_1") (pintype "unspecified"))
      (node (ref "D17") (pin "1") (pinfunction "K_1") (pintype "unspecified"))
      (node (ref "D18") (pin "1") (pinfunction "K_1") (pintype "unspecified"))
      (node (ref "D19") (pin "1") (pinfunction "K_1") (pintype "unspecified"))
      (node (ref "D20") (pin "1") (pinfunction "K_1") (pintype "unspecified"))
      (node (ref "D21") (pin "1") (pinfunction "K_1") (pintype "unspecified"))
      (node (ref "D22") (pin "1") (pinfunction "K_1") (pintype "unspecified"))
      (node (ref "D23") (pin "1") (pinfunction "K_1") (pintype "unspecified"))
      (node (ref "D24") (pin "1") (pinfunction "K_1") (pintype "unspecified"))
      (node (ref "D25") (pin "1") (pinfunction "K_1") (pintype "unspecified"))
      (node (ref "D26") (pin "1") (pinfunction "K_1") (pintype "unspecified"))
      (node (ref "D27") (pin "1") (pinfunction "K_1") (pintype "unspecified"))
      (node (ref "D28") (pin "1") (pinfunction "K_1") (pintype "unspecified"))
      (node (ref "U1") (pin "26") (pinfunction "PB13_26") (pintype "unspecified"))
    )
    (net (code "156") (name "ROW2") (class "Default")
      (node (ref "D29") (pin "1") (pinfunction "K_1") (pintype "unspecified"))
      (node (ref "D30") (pin "1") (pinfunction "K_1") (pintype "unspecified"))
      (node (ref "D31") (pin "1") (pinfunction "K_1") (pintype "unspecified"))
      (node (ref "D32") (pin "1") (pinfunction "K_1") (pintype "unspecified"))
      (node (ref "D33") (pin "1") (pinfunction "K_1") (pintype "unspecified"))
      (node (ref "D34") (pin "1") (pinfunction "K_1") (pintype "unspecified"))
      (node (ref "D35") (pin "1") (pinfunction "K_1") (pintype "unspecified"))
      (node (ref "D36") (pin "1") (pinfunction "K_1") (pintype "unspecified"))
      (node (ref "D37") (pin "1") (pinfunction "K_1") (pintype "unspecified"))
      (node (ref "D38") (pin "1") (pinfunction "K_1") (pintype "unspecified"))
      (node (ref "D39") (pin "1") (pinfunction "K_1") (pintype "unspecified"))
      (node (ref "D40") (pin "1") (pinfunction "K_1") (pintype "unspecified"))
      (node (ref "D41") (pin "1") (pinfunction "K_1") (pintype "unspecified"))
      (node (ref "U1") (pin "25") (pinfunction "PB12_25") (pintype "unspecified"))
    )
    (net (code "157") (name "ROW3") (class "Default")
      (node (ref "D42") (pin "1") (pinfunction "K_1") (pintype "unspecified"))
      (node (ref "D43") (pin "1") (pinfunction "K_1") (pintype "unspecified"))
      (node (ref "D44") (pin "1") (pinfunction "K_1") (pintype "unspecified"))
      (node (ref "D45") (pin "1") (pinfunction "K_1") (pintype "unspecified"))
      (node (ref "D46") (pin "1") (pinfunction "K_1") (pintype "unspecified"))
      (node (ref "D47") (pin "1") (pinfunction "K_1") (pintype "unspecified"))
      (node (ref "D48") (pin "1") (pinfunction "K_1") (pintype "unspecified"))
      (node (ref "D49") (pin "1") (pinfunction "K_1") (pintype "unspecified"))
      (node (ref "D50") (pin "1") (pinfunction "K_1") (pintype "unspecified"))
      (node (ref "D51") (pin "1") (pinfunction "K_1") (pintype "unspecified"))
      (node (ref "D52") (pin "1") (pinfunction "K_1") (pintype "unspecified"))
      (node (ref "D53") (pin "1") (pinfunction "K_1") (pintype "unspecified"))
      (node (ref "U1") (pin "14") (pinfunction "PA4_14") (pintype "unspecified"))
    )
    (net (code "158") (name "ROW4") (class "Default")
      (node (ref "D54") (pin "1") (pinfunction "K_1") (pintype "unspecified"))
      (node (ref "D55") (pin "1") (pinfunction "K_1") (pintype "unspecified"))
      (node (ref "D56") (pin "1") (pinfunction "K_1") (pintype "unspecified"))
      (node (ref "D57") (pin "1") (pinfunction "K_1") (pintype "unspecified"))
      (node (ref "D58") (pin "1") (pinfunction "K_1") (pintype "unspecified"))
      (node (ref "D59") (pin "1") (pinfunction "K_1") (pintype "unspecified"))
      (node (ref "D60") (pin "1") (pinfunction "K_1") (pintype "unspecified"))
      (node (ref "D61") (pin "1") (pinfunction "K_1") (pintype "unspecified"))
      (node (ref "U1") (pin "11") (pinfunction "PA1_11") (pintype "unspecified"))
    )
    (net (code "159") (name "SWCLK") (class "Default")
      (node (ref "J1") (pin "3") (pinfunction "3_3") (pintype "unspecified"))
      (node (ref "U1") (pin "37") (pinfunction "PA14_37") (pintype "unspecified"))
    )
    (net (code "160") (name "SWDIO") (class "Default")
      (node (ref "J1") (pin "2") (pinfunction "2_2") (pintype "unspecified"))
      (node (ref "U1") (pin "34") (pinfunction "PA13_34") (pintype "unspecified"))
    )
    (net (code "161") (name "VCC") (class "Default")
      (node (ref "C10") (pin "1") (pinfunction "1_1") (pintype "unspecified"))
      (node (ref "C4") (pin "2") (pinfunction "2_2") (pintype "input"))
      (node (ref "C5") (pin "2") (pinfunction "2_2") (pintype "input"))
      (node (ref "C6") (pin "2") (pinfunction "2_2") (pintype "input"))
      (node (ref "C7") (pin "2") (pinfunction "2_2") (pintype "input"))
      (node (ref "C9") (pin "2") (pinfunction "2_2") (pintype "input"))
      (node (ref "J1") (pin "4") (pinfunction "4_4") (pintype "unspecified"))
      (node (ref "R1") (pin "1") (pinfunction "1_1") (pintype "input"))
      (node (ref "U1") (pin "1") (pinfunction "VBAT_1") (pintype "unspecified"))
      (node (ref "U1") (pin "24") (pinfunction "VDD_1_24") (pintype "unspecified"))
      (node (ref "U1") (pin "36") (pinfunction "VDD_2_36") (pintype "unspecified"))
      (node (ref "U1") (pin "48") (pinfunction "VDD_3_48") (pintype "unspecified"))
      (node (ref "U1") (pin "9") (pinfunction "VDDA_9") (pintype "unspecified"))
      (node (ref "U2") (pin "5") (pinfunction "VOUT_5") (pintype "unspecified"))
    )
    (net (code "162") (name "unconnected-(SW61-Pad2)") (class "Default")
      (node (ref "SW61") (pin "2") (pinfunction "2_2") (pintype "unspecified+no_connect"))
    )
    (net (code "163") (name "unconnected-(SW62-Pad6)") (class "Default")
      (node (ref "SW62") (pin "6") (pinfunction "6_6") (pintype "unspecified+no_connect"))
    )
    (net (code "164") (name "unconnected-(SW62-Pad7)") (class "Default")
      (node (ref "SW62") (pin "7") (pinfunction "7_7") (pintype "unspecified+no_connect"))
    )
    (net (code "165") (name "unconnected-(U1-PA15-Pad38)") (class "Default")
      (node (ref "U1") (pin "38") (pinfunction "PA15_38") (pintype "unspecified"))
    )
    (net (code "166") (name "unconnected-(U1-PB0-Pad18)") (class "Default")
      (node (ref "U1") (pin "18") (pinfunction "PB0_18") (pintype "unspecified"))
    )
    (net (code "167") (name "unconnected-(U1-PB1-Pad19)") (class "Default")
      (node (ref "U1") (pin "19") (pinfunction "PB1_19") (pintype "unspecified"))
    )
    (net (code "168") (name "unconnected-(U1-PB3-Pad39)") (class "Default")
      (node (ref "U1") (pin "39") (pinfunction "PB3_39") (pintype "unspecified"))
    )
    (net (code "169") (name "unconnected-(U1-PB7-Pad43)") (class "Default")
      (node (ref "U1") (pin "43") (pinfunction "PB7_43") (pintype "unspecified"))
    )
    (net (code "170") (name "unconnected-(U1-PB8-Pad45)") (class "Default")
      (node (ref "U1") (pin "45") (pinfunction "PB8_45") (pintype "unspecified"))
    )
    (net (code "171") (name "unconnected-(U1-PB10-Pad21)") (class "Default")
      (node (ref "U1") (pin "21") (pinfunction "PB10_21") (pintype "unspecified"))
    )
    (net (code "172") (name "unconnected-(U1-PB11-Pad22)") (class "Default")
      (node (ref "U1") (pin "22") (pinfunction "PB11_22") (pintype "unspecified"))
    )
    (net (code "173") (name "unconnected-(USBC1-SBU1-PadA8)") (class "Default")
      (node (ref "USBC1") (pin "A8") (pinfunction "SBU1_A8") (pintype "unspecified+no_connect"))
    )
    (net (code "174") (name "unconnected-(USBC1-SBU2-PadB8)") (class "Default")
      (node (ref "USBC1") (pin "B8") (pinfunction "SBU2_B8") (pintype "unspecified+no_connect"))
    )
  )
)
